# diybmsv4-00_panels.net
KiCad netlist of a schematic drawn in EAGLE
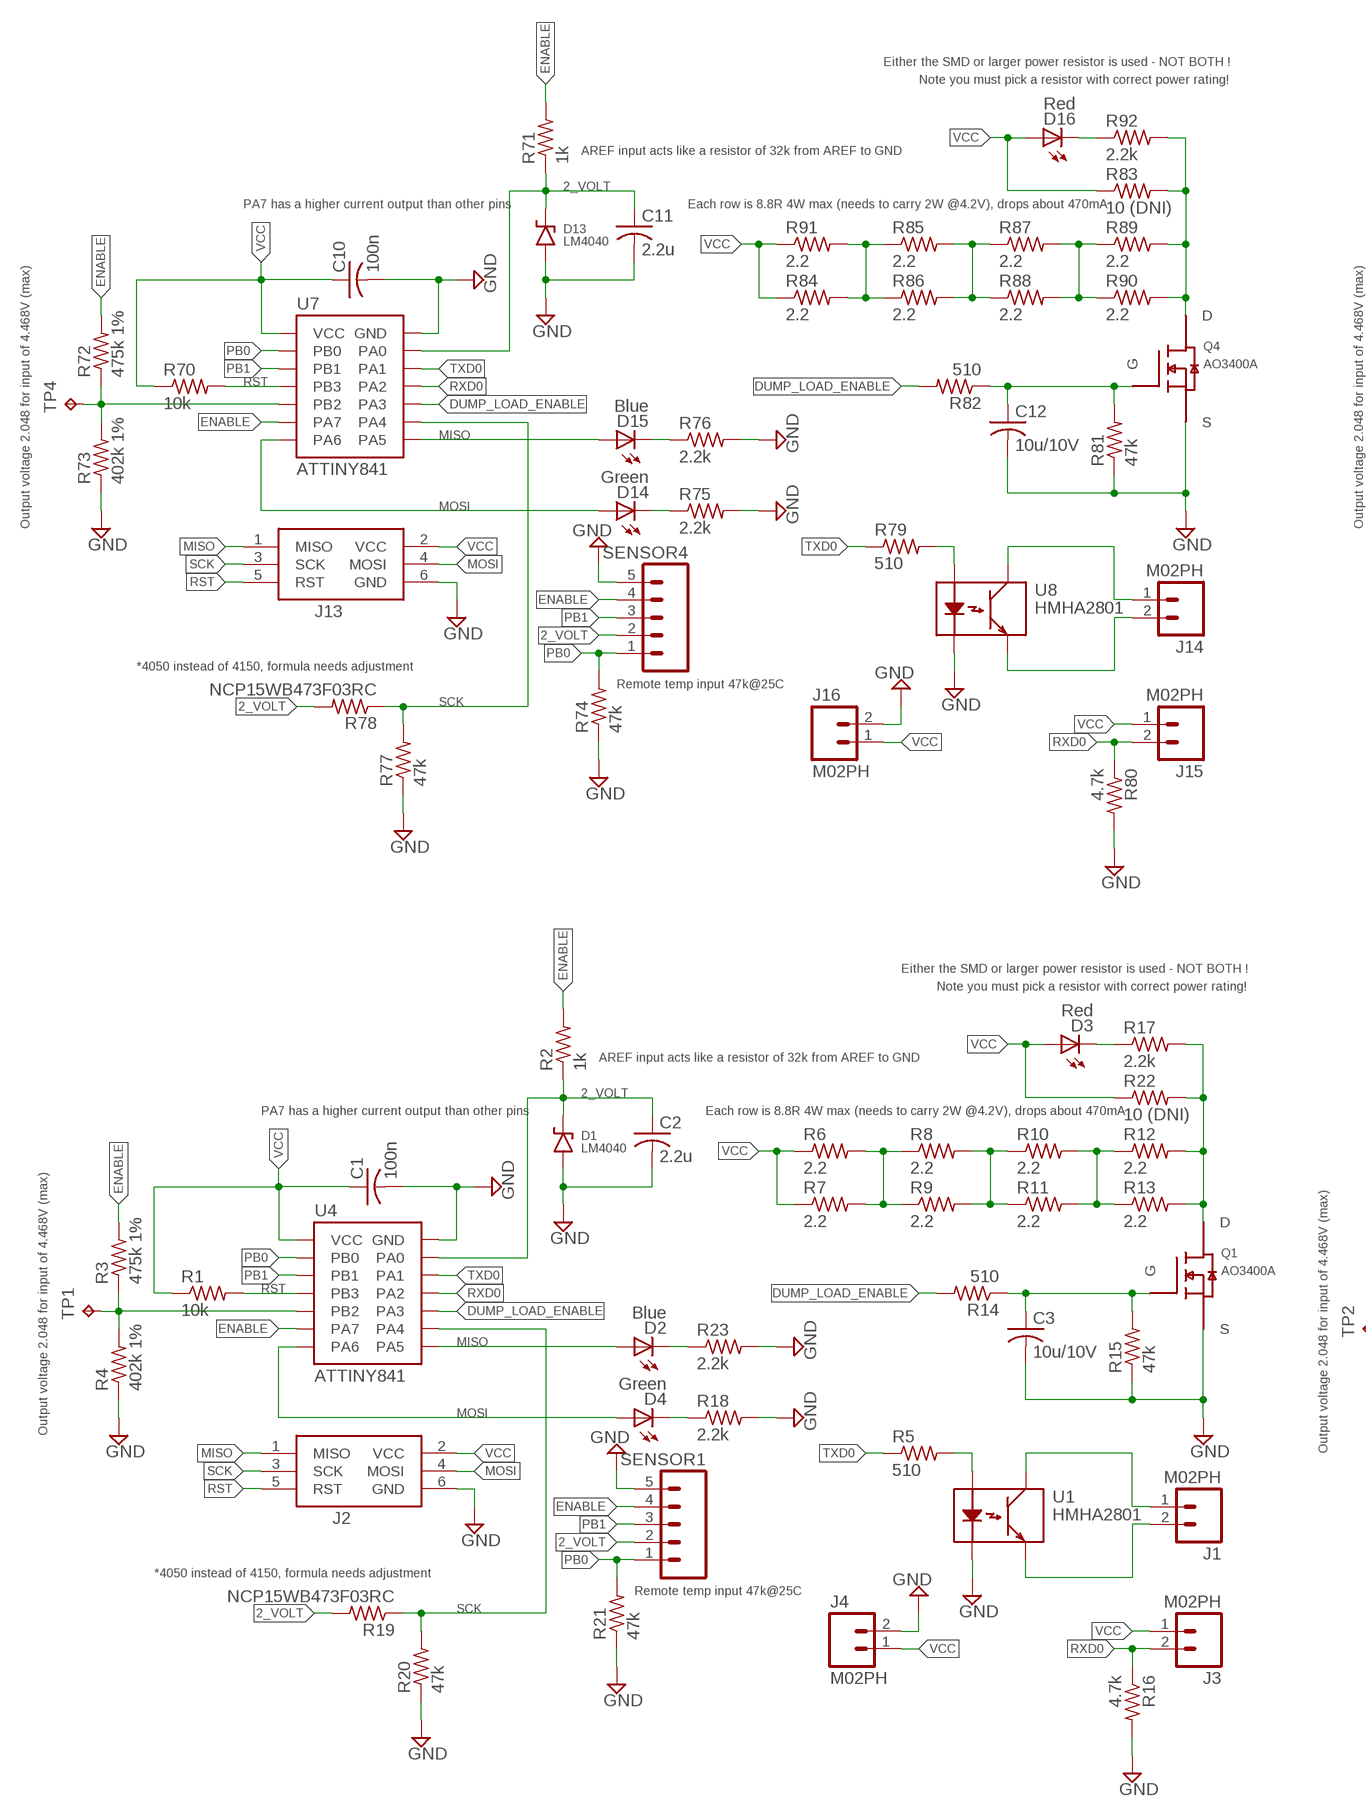
[diagram p0: schematic, sheet 1, part 1 of 2]
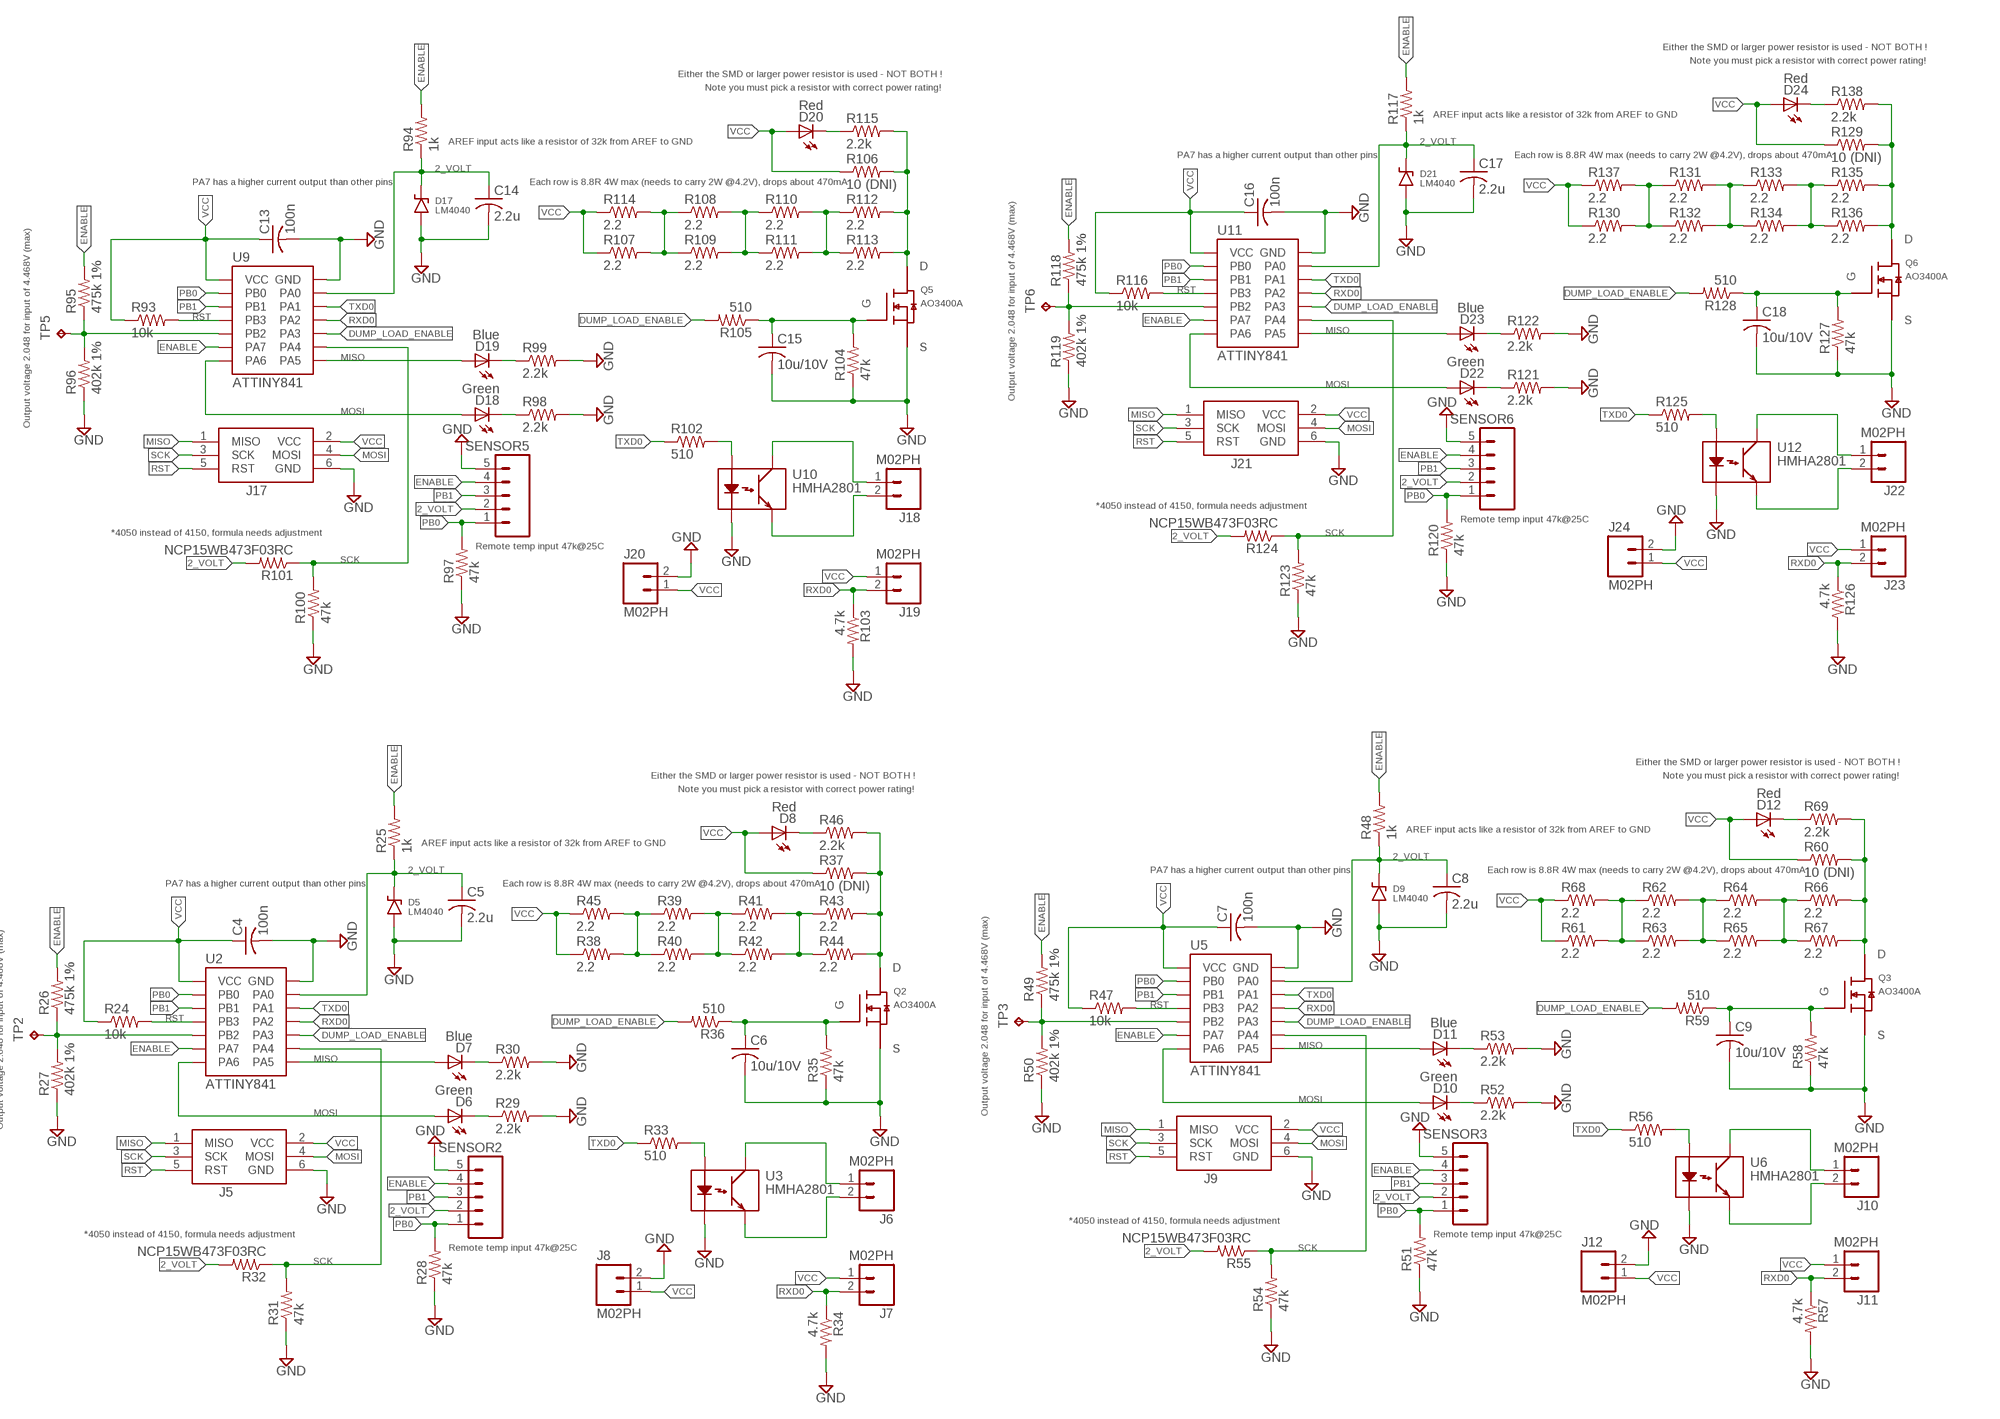
[diagram p1: schematic, sheet 1, part 2 of 2]

(export (version "E")
  (design (tool "Eeschema 10.0.6"))
  (components
    (comp (ref "C1")
      (value "100n")
      (footprint "eagle-import:C0402")
      (libsource (lib "eagle-import") (part "C-USC0402"))
    )
    (comp (ref "C2")
      (value "2.2u")
      (footprint "eagle-import:C0402")
      (libsource (lib "eagle-import") (part "C-USC0402"))
    )
    (comp (ref "C3")
      (value "10u/10V")
      (footprint "eagle-import:C0402")
      (libsource (lib "eagle-import") (part "C-USC0402"))
    )
    (comp (ref "C4")
      (value "100n")
      (footprint "eagle-import:C0402")
      (libsource (lib "eagle-import") (part "C-USC0402"))
    )
    (comp (ref "C5")
      (value "2.2u")
      (footprint "eagle-import:C0402")
      (libsource (lib "eagle-import") (part "C-USC0402"))
    )
    (comp (ref "C6")
      (value "10u/10V")
      (footprint "eagle-import:C0402")
      (libsource (lib "eagle-import") (part "C-USC0402"))
    )
    (comp (ref "C7")
      (value "100n")
      (footprint "eagle-import:C0402")
      (libsource (lib "eagle-import") (part "C-USC0402"))
    )
    (comp (ref "C8")
      (value "2.2u")
      (footprint "eagle-import:C0402")
      (libsource (lib "eagle-import") (part "C-USC0402"))
    )
    (comp (ref "C9")
      (value "10u/10V")
      (footprint "eagle-import:C0402")
      (libsource (lib "eagle-import") (part "C-USC0402"))
    )
    (comp (ref "C10")
      (value "100n")
      (footprint "eagle-import:C0402")
      (libsource (lib "eagle-import") (part "C-USC0402"))
    )
    (comp (ref "C11")
      (value "2.2u")
      (footprint "eagle-import:C0402")
      (libsource (lib "eagle-import") (part "C-USC0402"))
    )
    (comp (ref "C12")
      (value "10u/10V")
      (footprint "eagle-import:C0402")
      (libsource (lib "eagle-import") (part "C-USC0402"))
    )
    (comp (ref "C13")
      (value "100n")
      (footprint "eagle-import:C0402")
      (libsource (lib "eagle-import") (part "C-USC0402"))
    )
    (comp (ref "C14")
      (value "2.2u")
      (footprint "eagle-import:C0402")
      (libsource (lib "eagle-import") (part "C-USC0402"))
    )
    (comp (ref "C15")
      (value "10u/10V")
      (footprint "eagle-import:C0402")
      (libsource (lib "eagle-import") (part "C-USC0402"))
    )
    (comp (ref "C16")
      (value "100n")
      (footprint "eagle-import:C0402")
      (libsource (lib "eagle-import") (part "C-USC0402"))
    )
    (comp (ref "C17")
      (value "2.2u")
      (footprint "eagle-import:C0402")
      (libsource (lib "eagle-import") (part "C-USC0402"))
    )
    (comp (ref "C18")
      (value "10u/10V")
      (footprint "eagle-import:C0402")
      (libsource (lib "eagle-import") (part "C-USC0402"))
    )
    (comp (ref "D1")
      (value "LM4040")
      (footprint "eagle-import:SOT23")
      (libsource (lib "eagle-import") (part "LM4040"))
    )
    (comp (ref "D2")
      (value "Blue")
      (footprint "eagle-import:CHIPLED_0603")
      (libsource (lib "eagle-import") (part "LEDCHIPLED_0603"))
    )
    (comp (ref "D3")
      (value "Red")
      (footprint "eagle-import:CHIPLED_0603")
      (libsource (lib "eagle-import") (part "LEDCHIPLED_0603"))
    )
    (comp (ref "D4")
      (value "Green")
      (footprint "eagle-import:CHIPLED_0603")
      (libsource (lib "eagle-import") (part "LEDCHIPLED_0603"))
    )
    (comp (ref "D5")
      (value "LM4040")
      (footprint "eagle-import:SOT23")
      (libsource (lib "eagle-import") (part "LM4040"))
    )
    (comp (ref "D6")
      (value "Green")
      (footprint "eagle-import:CHIPLED_0603")
      (libsource (lib "eagle-import") (part "LEDCHIPLED_0603"))
    )
    (comp (ref "D7")
      (value "Blue")
      (footprint "eagle-import:CHIPLED_0603")
      (libsource (lib "eagle-import") (part "LEDCHIPLED_0603"))
    )
    (comp (ref "D8")
      (value "Red")
      (footprint "eagle-import:CHIPLED_0603")
      (libsource (lib "eagle-import") (part "LEDCHIPLED_0603"))
    )
    (comp (ref "D9")
      (value "LM4040")
      (footprint "eagle-import:SOT23")
      (libsource (lib "eagle-import") (part "LM4040"))
    )
    (comp (ref "D10")
      (value "Green")
      (footprint "eagle-import:CHIPLED_0603")
      (libsource (lib "eagle-import") (part "LEDCHIPLED_0603"))
    )
    (comp (ref "D11")
      (value "Blue")
      (footprint "eagle-import:CHIPLED_0603")
      (libsource (lib "eagle-import") (part "LEDCHIPLED_0603"))
    )
    (comp (ref "D12")
      (value "Red")
      (footprint "eagle-import:CHIPLED_0603")
      (libsource (lib "eagle-import") (part "LEDCHIPLED_0603"))
    )
    (comp (ref "D13")
      (value "LM4040")
      (footprint "eagle-import:SOT23")
      (libsource (lib "eagle-import") (part "LM4040"))
    )
    (comp (ref "D14")
      (value "Green")
      (footprint "eagle-import:CHIPLED_0603")
      (libsource (lib "eagle-import") (part "LEDCHIPLED_0603"))
    )
    (comp (ref "D15")
      (value "Blue")
      (footprint "eagle-import:CHIPLED_0603")
      (libsource (lib "eagle-import") (part "LEDCHIPLED_0603"))
    )
    (comp (ref "D16")
      (value "Red")
      (footprint "eagle-import:CHIPLED_0603")
      (libsource (lib "eagle-import") (part "LEDCHIPLED_0603"))
    )
    (comp (ref "D17")
      (value "LM4040")
      (footprint "eagle-import:SOT23")
      (libsource (lib "eagle-import") (part "LM4040"))
    )
    (comp (ref "D18")
      (value "Green")
      (footprint "eagle-import:CHIPLED_0603")
      (libsource (lib "eagle-import") (part "LEDCHIPLED_0603"))
    )
    (comp (ref "D19")
      (value "Blue")
      (footprint "eagle-import:CHIPLED_0603")
      (libsource (lib "eagle-import") (part "LEDCHIPLED_0603"))
    )
    (comp (ref "D20")
      (value "Red")
      (footprint "eagle-import:CHIPLED_0603")
      (libsource (lib "eagle-import") (part "LEDCHIPLED_0603"))
    )
    (comp (ref "D21")
      (value "LM4040")
      (footprint "eagle-import:SOT23")
      (libsource (lib "eagle-import") (part "LM4040"))
    )
    (comp (ref "D22")
      (value "Green")
      (footprint "eagle-import:CHIPLED_0603")
      (libsource (lib "eagle-import") (part "LEDCHIPLED_0603"))
    )
    (comp (ref "D23")
      (value "Blue")
      (footprint "eagle-import:CHIPLED_0603")
      (libsource (lib "eagle-import") (part "LEDCHIPLED_0603"))
    )
    (comp (ref "D24")
      (value "Red")
      (footprint "eagle-import:CHIPLED_0603")
      (libsource (lib "eagle-import") (part "LEDCHIPLED_0603"))
    )
    (comp (ref "J1")
      (value "M02PH")
      (footprint "eagle-import:S2B-PH-RA")
      (libsource (lib "eagle-import") (part "M02PH"))
    )
    (comp (ref "J2")
      (value "AVRISP-6")
      (footprint "eagle-import:AVRISP")
      (libsource (lib "eagle-import") (part "AVRISP-6"))
    )
    (comp (ref "J3")
      (value "M02PH")
      (footprint "eagle-import:S2B-PH-RA")
      (libsource (lib "eagle-import") (part "M02PH"))
    )
    (comp (ref "J4")
      (value "M02PH")
      (footprint "eagle-import:S2B-PH-RA")
      (libsource (lib "eagle-import") (part "M02PH"))
    )
    (comp (ref "J5")
      (value "AVRISP-6")
      (footprint "eagle-import:AVRISP")
      (libsource (lib "eagle-import") (part "AVRISP-6"))
    )
    (comp (ref "J6")
      (value "M02PH")
      (footprint "eagle-import:S2B-PH-RA")
      (libsource (lib "eagle-import") (part "M02PH"))
    )
    (comp (ref "J7")
      (value "M02PH")
      (footprint "eagle-import:S2B-PH-RA")
      (libsource (lib "eagle-import") (part "M02PH"))
    )
    (comp (ref "J8")
      (value "M02PH")
      (footprint "eagle-import:S2B-PH-RA")
      (libsource (lib "eagle-import") (part "M02PH"))
    )
    (comp (ref "J9")
      (value "AVRISP-6")
      (footprint "eagle-import:AVRISP")
      (libsource (lib "eagle-import") (part "AVRISP-6"))
    )
    (comp (ref "J10")
      (value "M02PH")
      (footprint "eagle-import:S2B-PH-RA")
      (libsource (lib "eagle-import") (part "M02PH"))
    )
    (comp (ref "J11")
      (value "M02PH")
      (footprint "eagle-import:S2B-PH-RA")
      (libsource (lib "eagle-import") (part "M02PH"))
    )
    (comp (ref "J12")
      (value "M02PH")
      (footprint "eagle-import:S2B-PH-RA")
      (libsource (lib "eagle-import") (part "M02PH"))
    )
    (comp (ref "J13")
      (value "AVRISP-6")
      (footprint "eagle-import:AVRISP")
      (libsource (lib "eagle-import") (part "AVRISP-6"))
    )
    (comp (ref "J14")
      (value "M02PH")
      (footprint "eagle-import:S2B-PH-RA")
      (libsource (lib "eagle-import") (part "M02PH"))
    )
    (comp (ref "J15")
      (value "M02PH")
      (footprint "eagle-import:S2B-PH-RA")
      (libsource (lib "eagle-import") (part "M02PH"))
    )
    (comp (ref "J16")
      (value "M02PH")
      (footprint "eagle-import:S2B-PH-RA")
      (libsource (lib "eagle-import") (part "M02PH"))
    )
    (comp (ref "J17")
      (value "AVRISP-6")
      (footprint "eagle-import:AVRISP")
      (libsource (lib "eagle-import") (part "AVRISP-6"))
    )
    (comp (ref "J18")
      (value "M02PH")
      (footprint "eagle-import:S2B-PH-RA")
      (libsource (lib "eagle-import") (part "M02PH"))
    )
    (comp (ref "J19")
      (value "M02PH")
      (footprint "eagle-import:S2B-PH-RA")
      (libsource (lib "eagle-import") (part "M02PH"))
    )
    (comp (ref "J20")
      (value "M02PH")
      (footprint "eagle-import:S2B-PH-RA")
      (libsource (lib "eagle-import") (part "M02PH"))
    )
    (comp (ref "J21")
      (value "AVRISP-6")
      (footprint "eagle-import:AVRISP")
      (libsource (lib "eagle-import") (part "AVRISP-6"))
    )
    (comp (ref "J22")
      (value "M02PH")
      (footprint "eagle-import:S2B-PH-RA")
      (libsource (lib "eagle-import") (part "M02PH"))
    )
    (comp (ref "J23")
      (value "M02PH")
      (footprint "eagle-import:S2B-PH-RA")
      (libsource (lib "eagle-import") (part "M02PH"))
    )
    (comp (ref "J24")
      (value "M02PH")
      (footprint "eagle-import:S2B-PH-RA")
      (libsource (lib "eagle-import") (part "M02PH"))
    )
    (comp (ref "Q1")
      (value "AO3400A")
      (footprint "eagle-import:SOT23")
      (libsource (lib "eagle-import") (part "AO3414"))
    )
    (comp (ref "Q2")
      (value "AO3400A")
      (footprint "eagle-import:SOT23")
      (libsource (lib "eagle-import") (part "AO3414"))
    )
    (comp (ref "Q3")
      (value "AO3400A")
      (footprint "eagle-import:SOT23")
      (libsource (lib "eagle-import") (part "AO3414"))
    )
    (comp (ref "Q4")
      (value "AO3400A")
      (footprint "eagle-import:SOT23")
      (libsource (lib "eagle-import") (part "AO3414"))
    )
    (comp (ref "Q5")
      (value "AO3400A")
      (footprint "eagle-import:SOT23")
      (libsource (lib "eagle-import") (part "AO3414"))
    )
    (comp (ref "Q6")
      (value "AO3400A")
      (footprint "eagle-import:SOT23")
      (libsource (lib "eagle-import") (part "AO3414"))
    )
    (comp (ref "R1")
      (value "10k")
      (footprint "eagle-import:R0402")
      (libsource (lib "eagle-import") (part "R-US_R0402"))
    )
    (comp (ref "R2")
      (value "1k")
      (footprint "eagle-import:R0402")
      (libsource (lib "eagle-import") (part "R-US_R0402"))
    )
    (comp (ref "R3")
      (value "475k 1%")
      (footprint "eagle-import:R0402")
      (libsource (lib "eagle-import") (part "R-US_R0402"))
    )
    (comp (ref "R4")
      (value "402k 1%")
      (footprint "eagle-import:R0402")
      (libsource (lib "eagle-import") (part "R-US_R0402"))
    )
    (comp (ref "R5")
      (value "510")
      (footprint "eagle-import:R0402")
      (libsource (lib "eagle-import") (part "R-US_R0402"))
    )
    (comp (ref "R6")
      (value "2.2")
      (footprint "eagle-import:R2512")
      (libsource (lib "eagle-import") (part "R-US_R2512"))
    )
    (comp (ref "R7")
      (value "2.2")
      (footprint "eagle-import:R2512")
      (libsource (lib "eagle-import") (part "R-US_R2512"))
    )
    (comp (ref "R8")
      (value "2.2")
      (footprint "eagle-import:R2512")
      (libsource (lib "eagle-import") (part "R-US_R2512"))
    )
    (comp (ref "R9")
      (value "2.2")
      (footprint "eagle-import:R2512")
      (libsource (lib "eagle-import") (part "R-US_R2512"))
    )
    (comp (ref "R10")
      (value "2.2")
      (footprint "eagle-import:R2512")
      (libsource (lib "eagle-import") (part "R-US_R2512"))
    )
    (comp (ref "R11")
      (value "2.2")
      (footprint "eagle-import:R2512")
      (libsource (lib "eagle-import") (part "R-US_R2512"))
    )
    (comp (ref "R12")
      (value "2.2")
      (footprint "eagle-import:R2512")
      (libsource (lib "eagle-import") (part "R-US_R2512"))
    )
    (comp (ref "R13")
      (value "2.2")
      (footprint "eagle-import:R2512")
      (libsource (lib "eagle-import") (part "R-US_R2512"))
    )
    (comp (ref "R14")
      (value "510")
      (footprint "eagle-import:R0402")
      (libsource (lib "eagle-import") (part "R-US_R0402"))
    )
    (comp (ref "R15")
      (value "47k")
      (footprint "eagle-import:R0402")
      (libsource (lib "eagle-import") (part "R-US_R0402"))
    )
    (comp (ref "R16")
      (value "4.7k")
      (footprint "eagle-import:R0402")
      (libsource (lib "eagle-import") (part "R-US_R0402"))
    )
    (comp (ref "R17")
      (value "2.2k")
      (footprint "eagle-import:R0402")
      (libsource (lib "eagle-import") (part "R-US_R0402"))
    )
    (comp (ref "R18")
      (value "2.2k")
      (footprint "eagle-import:R0402")
      (libsource (lib "eagle-import") (part "R-US_R0402"))
    )
    (comp (ref "R19")
      (value "NCP15WB473F03RC")
      (footprint "eagle-import:R0402")
      (libsource (lib "eagle-import") (part "R-US_R0402"))
    )
    (comp (ref "R20")
      (value "47k")
      (footprint "eagle-import:R0402")
      (libsource (lib "eagle-import") (part "R-US_R0402"))
    )
    (comp (ref "R21")
      (value "47k")
      (footprint "eagle-import:R0402")
      (libsource (lib "eagle-import") (part "R-US_R0402"))
    )
    (comp (ref "R22")
      (value "10 (DNI)")
      (footprint "eagle-import:R-5W-22X9P5X9P5")
      (libsource (lib "eagle-import") (part "RESISTOR25MM"))
    )
    (comp (ref "R23")
      (value "2.2k")
      (footprint "eagle-import:R0402")
      (libsource (lib "eagle-import") (part "R-US_R0402"))
    )
    (comp (ref "R24")
      (value "10k")
      (footprint "eagle-import:R0402")
      (libsource (lib "eagle-import") (part "R-US_R0402"))
    )
    (comp (ref "R25")
      (value "1k")
      (footprint "eagle-import:R0402")
      (libsource (lib "eagle-import") (part "R-US_R0402"))
    )
    (comp (ref "R26")
      (value "475k 1%")
      (footprint "eagle-import:R0402")
      (libsource (lib "eagle-import") (part "R-US_R0402"))
    )
    (comp (ref "R27")
      (value "402k 1%")
      (footprint "eagle-import:R0402")
      (libsource (lib "eagle-import") (part "R-US_R0402"))
    )
    (comp (ref "R28")
      (value "47k")
      (footprint "eagle-import:R0402")
      (libsource (lib "eagle-import") (part "R-US_R0402"))
    )
    (comp (ref "R29")
      (value "2.2k")
      (footprint "eagle-import:R0402")
      (libsource (lib "eagle-import") (part "R-US_R0402"))
    )
    (comp (ref "R30")
      (value "2.2k")
      (footprint "eagle-import:R0402")
      (libsource (lib "eagle-import") (part "R-US_R0402"))
    )
    (comp (ref "R31")
      (value "47k")
      (footprint "eagle-import:R0402")
      (libsource (lib "eagle-import") (part "R-US_R0402"))
    )
    (comp (ref "R32")
      (value "NCP15WB473F03RC")
      (footprint "eagle-import:R0402")
      (libsource (lib "eagle-import") (part "R-US_R0402"))
    )
    (comp (ref "R33")
      (value "510")
      (footprint "eagle-import:R0402")
      (libsource (lib "eagle-import") (part "R-US_R0402"))
    )
    (comp (ref "R34")
      (value "4.7k")
      (footprint "eagle-import:R0402")
      (libsource (lib "eagle-import") (part "R-US_R0402"))
    )
    (comp (ref "R35")
      (value "47k")
      (footprint "eagle-import:R0402")
      (libsource (lib "eagle-import") (part "R-US_R0402"))
    )
    (comp (ref "R36")
      (value "510")
      (footprint "eagle-import:R0402")
      (libsource (lib "eagle-import") (part "R-US_R0402"))
    )
    (comp (ref "R37")
      (value "10 (DNI)")
      (footprint "eagle-import:R-5W-22X9P5X9P5")
      (libsource (lib "eagle-import") (part "RESISTOR25MM"))
    )
    (comp (ref "R38")
      (value "2.2")
      (footprint "eagle-import:R2512")
      (libsource (lib "eagle-import") (part "R-US_R2512"))
    )
    (comp (ref "R39")
      (value "2.2")
      (footprint "eagle-import:R2512")
      (libsource (lib "eagle-import") (part "R-US_R2512"))
    )
    (comp (ref "R40")
      (value "2.2")
      (footprint "eagle-import:R2512")
      (libsource (lib "eagle-import") (part "R-US_R2512"))
    )
    (comp (ref "R41")
      (value "2.2")
      (footprint "eagle-import:R2512")
      (libsource (lib "eagle-import") (part "R-US_R2512"))
    )
    (comp (ref "R42")
      (value "2.2")
      (footprint "eagle-import:R2512")
      (libsource (lib "eagle-import") (part "R-US_R2512"))
    )
    (comp (ref "R43")
      (value "2.2")
      (footprint "eagle-import:R2512")
      (libsource (lib "eagle-import") (part "R-US_R2512"))
    )
    (comp (ref "R44")
      (value "2.2")
      (footprint "eagle-import:R2512")
      (libsource (lib "eagle-import") (part "R-US_R2512"))
    )
    (comp (ref "R45")
      (value "2.2")
      (footprint "eagle-import:R2512")
      (libsource (lib "eagle-import") (part "R-US_R2512"))
    )
    (comp (ref "R46")
      (value "2.2k")
      (footprint "eagle-import:R0402")
      (libsource (lib "eagle-import") (part "R-US_R0402"))
    )
    (comp (ref "R47")
      (value "10k")
      (footprint "eagle-import:R0402")
      (libsource (lib "eagle-import") (part "R-US_R0402"))
    )
    (comp (ref "R48")
      (value "1k")
      (footprint "eagle-import:R0402")
      (libsource (lib "eagle-import") (part "R-US_R0402"))
    )
    (comp (ref "R49")
      (value "475k 1%")
      (footprint "eagle-import:R0402")
      (libsource (lib "eagle-import") (part "R-US_R0402"))
    )
    (comp (ref "R50")
      (value "402k 1%")
      (footprint "eagle-import:R0402")
      (libsource (lib "eagle-import") (part "R-US_R0402"))
    )
    (comp (ref "R51")
      (value "47k")
      (footprint "eagle-import:R0402")
      (libsource (lib "eagle-import") (part "R-US_R0402"))
    )
    (comp (ref "R52")
      (value "2.2k")
      (footprint "eagle-import:R0402")
      (libsource (lib "eagle-import") (part "R-US_R0402"))
    )
    (comp (ref "R53")
      (value "2.2k")
      (footprint "eagle-import:R0402")
      (libsource (lib "eagle-import") (part "R-US_R0402"))
    )
    (comp (ref "R54")
      (value "47k")
      (footprint "eagle-import:R0402")
      (libsource (lib "eagle-import") (part "R-US_R0402"))
    )
    (comp (ref "R55")
      (value "NCP15WB473F03RC")
      (footprint "eagle-import:R0402")
      (libsource (lib "eagle-import") (part "R-US_R0402"))
    )
    (comp (ref "R56")
      (value "510")
      (footprint "eagle-import:R0402")
      (libsource (lib "eagle-import") (part "R-US_R0402"))
    )
    (comp (ref "R57")
      (value "4.7k")
      (footprint "eagle-import:R0402")
      (libsource (lib "eagle-import") (part "R-US_R0402"))
    )
    (comp (ref "R58")
      (value "47k")
      (footprint "eagle-import:R0402")
      (libsource (lib "eagle-import") (part "R-US_R0402"))
    )
    (comp (ref "R59")
      (value "510")
      (footprint "eagle-import:R0402")
      (libsource (lib "eagle-import") (part "R-US_R0402"))
    )
    (comp (ref "R60")
      (value "10 (DNI)")
      (footprint "eagle-import:R-5W-22X9P5X9P5")
      (libsource (lib "eagle-import") (part "RESISTOR25MM"))
    )
    (comp (ref "R61")
      (value "2.2")
      (footprint "eagle-import:R2512")
      (libsource (lib "eagle-import") (part "R-US_R2512"))
    )
    (comp (ref "R62")
      (value "2.2")
      (footprint "eagle-import:R2512")
      (libsource (lib "eagle-import") (part "R-US_R2512"))
    )
    (comp (ref "R63")
      (value "2.2")
      (footprint "eagle-import:R2512")
      (libsource (lib "eagle-import") (part "R-US_R2512"))
    )
    (comp (ref "R64")
      (value "2.2")
      (footprint "eagle-import:R2512")
      (libsource (lib "eagle-import") (part "R-US_R2512"))
    )
    (comp (ref "R65")
      (value "2.2")
      (footprint "eagle-import:R2512")
      (libsource (lib "eagle-import") (part "R-US_R2512"))
    )
    (comp (ref "R66")
      (value "2.2")
      (footprint "eagle-import:R2512")
      (libsource (lib "eagle-import") (part "R-US_R2512"))
    )
    (comp (ref "R67")
      (value "2.2")
      (footprint "eagle-import:R2512")
      (libsource (lib "eagle-import") (part "R-US_R2512"))
    )
    (comp (ref "R68")
      (value "2.2")
      (footprint "eagle-import:R2512")
      (libsource (lib "eagle-import") (part "R-US_R2512"))
    )
    (comp (ref "R69")
      (value "2.2k")
      (footprint "eagle-import:R0402")
      (libsource (lib "eagle-import") (part "R-US_R0402"))
    )
    (comp (ref "R70")
      (value "10k")
      (footprint "eagle-import:R0402")
      (libsource (lib "eagle-import") (part "R-US_R0402"))
    )
    (comp (ref "R71")
      (value "1k")
      (footprint "eagle-import:R0402")
      (libsource (lib "eagle-import") (part "R-US_R0402"))
    )
    (comp (ref "R72")
      (value "475k 1%")
      (footprint "eagle-import:R0402")
      (libsource (lib "eagle-import") (part "R-US_R0402"))
    )
    (comp (ref "R73")
      (value "402k 1%")
      (footprint "eagle-import:R0402")
      (libsource (lib "eagle-import") (part "R-US_R0402"))
    )
    (comp (ref "R74")
      (value "47k")
      (footprint "eagle-import:R0402")
      (libsource (lib "eagle-import") (part "R-US_R0402"))
    )
    (comp (ref "R75")
      (value "2.2k")
      (footprint "eagle-import:R0402")
      (libsource (lib "eagle-import") (part "R-US_R0402"))
    )
    (comp (ref "R76")
      (value "2.2k")
      (footprint "eagle-import:R0402")
      (libsource (lib "eagle-import") (part "R-US_R0402"))
    )
    (comp (ref "R77")
      (value "47k")
      (footprint "eagle-import:R0402")
      (libsource (lib "eagle-import") (part "R-US_R0402"))
    )
    (comp (ref "R78")
      (value "NCP15WB473F03RC")
      (footprint "eagle-import:R0402")
      (libsource (lib "eagle-import") (part "R-US_R0402"))
    )
    (comp (ref "R79")
      (value "510")
      (footprint "eagle-import:R0402")
      (libsource (lib "eagle-import") (part "R-US_R0402"))
    )
    (comp (ref "R80")
      (value "4.7k")
      (footprint "eagle-import:R0402")
      (libsource (lib "eagle-import") (part "R-US_R0402"))
    )
    (comp (ref "R81")
      (value "47k")
      (footprint "eagle-import:R0402")
      (libsource (lib "eagle-import") (part "R-US_R0402"))
    )
    (comp (ref "R82")
      (value "510")
      (footprint "eagle-import:R0402")
      (libsource (lib "eagle-import") (part "R-US_R0402"))
    )
    (comp (ref "R83")
      (value "10 (DNI)")
      (footprint "eagle-import:R-5W-22X9P5X9P5")
      (libsource (lib "eagle-import") (part "RESISTOR25MM"))
    )
    (comp (ref "R84")
      (value "2.2")
      (footprint "eagle-import:R2512")
      (libsource (lib "eagle-import") (part "R-US_R2512"))
    )
    (comp (ref "R85")
      (value "2.2")
      (footprint "eagle-import:R2512")
      (libsource (lib "eagle-import") (part "R-US_R2512"))
    )
    (comp (ref "R86")
      (value "2.2")
      (footprint "eagle-import:R2512")
      (libsource (lib "eagle-import") (part "R-US_R2512"))
    )
    (comp (ref "R87")
      (value "2.2")
      (footprint "eagle-import:R2512")
      (libsource (lib "eagle-import") (part "R-US_R2512"))
    )
    (comp (ref "R88")
      (value "2.2")
      (footprint "eagle-import:R2512")
      (libsource (lib "eagle-import") (part "R-US_R2512"))
    )
    (comp (ref "R89")
      (value "2.2")
      (footprint "eagle-import:R2512")
      (libsource (lib "eagle-import") (part "R-US_R2512"))
    )
    (comp (ref "R90")
      (value "2.2")
      (footprint "eagle-import:R2512")
      (libsource (lib "eagle-import") (part "R-US_R2512"))
    )
    (comp (ref "R91")
      (value "2.2")
      (footprint "eagle-import:R2512")
      (libsource (lib "eagle-import") (part "R-US_R2512"))
    )
    (comp (ref "R92")
      (value "2.2k")
      (footprint "eagle-import:R0402")
      (libsource (lib "eagle-import") (part "R-US_R0402"))
    )
    (comp (ref "R93")
      (value "10k")
      (footprint "eagle-import:R0402")
      (libsource (lib "eagle-import") (part "R-US_R0402"))
    )
    (comp (ref "R94")
      (value "1k")
      (footprint "eagle-import:R0402")
      (libsource (lib "eagle-import") (part "R-US_R0402"))
    )
    (comp (ref "R95")
      (value "475k 1%")
      (footprint "eagle-import:R0402")
      (libsource (lib "eagle-import") (part "R-US_R0402"))
    )
    (comp (ref "R96")
      (value "402k 1%")
      (footprint "eagle-import:R0402")
      (libsource (lib "eagle-import") (part "R-US_R0402"))
    )
    (comp (ref "R97")
      (value "47k")
      (footprint "eagle-import:R0402")
      (libsource (lib "eagle-import") (part "R-US_R0402"))
    )
    (comp (ref "R98")
      (value "2.2k")
      (footprint "eagle-import:R0402")
      (libsource (lib "eagle-import") (part "R-US_R0402"))
    )
    (comp (ref "R99")
      (value "2.2k")
      (footprint "eagle-import:R0402")
      (libsource (lib "eagle-import") (part "R-US_R0402"))
    )
    (comp (ref "R100")
      (value "47k")
      (footprint "eagle-import:R0402")
      (libsource (lib "eagle-import") (part "R-US_R0402"))
    )
    (comp (ref "R101")
      (value "NCP15WB473F03RC")
      (footprint "eagle-import:R0402")
      (libsource (lib "eagle-import") (part "R-US_R0402"))
    )
    (comp (ref "R102")
      (value "510")
      (footprint "eagle-import:R0402")
      (libsource (lib "eagle-import") (part "R-US_R0402"))
    )
    (comp (ref "R103")
      (value "4.7k")
      (footprint "eagle-import:R0402")
      (libsource (lib "eagle-import") (part "R-US_R0402"))
    )
    (comp (ref "R104")
      (value "47k")
      (footprint "eagle-import:R0402")
      (libsource (lib "eagle-import") (part "R-US_R0402"))
    )
    (comp (ref "R105")
      (value "510")
      (footprint "eagle-import:R0402")
      (libsource (lib "eagle-import") (part "R-US_R0402"))
    )
    (comp (ref "R106")
      (value "10 (DNI)")
      (footprint "eagle-import:R-5W-22X9P5X9P5")
      (libsource (lib "eagle-import") (part "RESISTOR25MM"))
    )
    (comp (ref "R107")
      (value "2.2")
      (footprint "eagle-import:R2512")
      (libsource (lib "eagle-import") (part "R-US_R2512"))
    )
    (comp (ref "R108")
      (value "2.2")
      (footprint "eagle-import:R2512")
      (libsource (lib "eagle-import") (part "R-US_R2512"))
    )
    (comp (ref "R109")
      (value "2.2")
      (footprint "eagle-import:R2512")
      (libsource (lib "eagle-import") (part "R-US_R2512"))
    )
    (comp (ref "R110")
      (value "2.2")
      (footprint "eagle-import:R2512")
      (libsource (lib "eagle-import") (part "R-US_R2512"))
    )
    (comp (ref "R111")
      (value "2.2")
      (footprint "eagle-import:R2512")
      (libsource (lib "eagle-import") (part "R-US_R2512"))
    )
    (comp (ref "R112")
      (value "2.2")
      (footprint "eagle-import:R2512")
      (libsource (lib "eagle-import") (part "R-US_R2512"))
    )
    (comp (ref "R113")
      (value "2.2")
      (footprint "eagle-import:R2512")
      (libsource (lib "eagle-import") (part "R-US_R2512"))
    )
    (comp (ref "R114")
      (value "2.2")
      (footprint "eagle-import:R2512")
      (libsource (lib "eagle-import") (part "R-US_R2512"))
    )
    (comp (ref "R115")
      (value "2.2k")
      (footprint "eagle-import:R0402")
      (libsource (lib "eagle-import") (part "R-US_R0402"))
    )
    (comp (ref "R116")
      (value "10k")
      (footprint "eagle-import:R0402")
      (libsource (lib "eagle-import") (part "R-US_R0402"))
    )
    (comp (ref "R117")
      (value "1k")
      (footprint "eagle-import:R0402")
      (libsource (lib "eagle-import") (part "R-US_R0402"))
    )
    (comp (ref "R118")
      (value "475k 1%")
      (footprint "eagle-import:R0402")
      (libsource (lib "eagle-import") (part "R-US_R0402"))
    )
    (comp (ref "R119")
      (value "402k 1%")
      (footprint "eagle-import:R0402")
      (libsource (lib "eagle-import") (part "R-US_R0402"))
    )
    (comp (ref "R120")
      (value "47k")
      (footprint "eagle-import:R0402")
      (libsource (lib "eagle-import") (part "R-US_R0402"))
    )
    (comp (ref "R121")
      (value "2.2k")
      (footprint "eagle-import:R0402")
      (libsource (lib "eagle-import") (part "R-US_R0402"))
    )
    (comp (ref "R122")
      (value "2.2k")
      (footprint "eagle-import:R0402")
      (libsource (lib "eagle-import") (part "R-US_R0402"))
    )
    (comp (ref "R123")
      (value "47k")
      (footprint "eagle-import:R0402")
      (libsource (lib "eagle-import") (part "R-US_R0402"))
    )
    (comp (ref "R124")
      (value "NCP15WB473F03RC")
      (footprint "eagle-import:R0402")
      (libsource (lib "eagle-import") (part "R-US_R0402"))
    )
    (comp (ref "R125")
      (value "510")
      (footprint "eagle-import:R0402")
      (libsource (lib "eagle-import") (part "R-US_R0402"))
    )
    (comp (ref "R126")
      (value "4.7k")
      (footprint "eagle-import:R0402")
      (libsource (lib "eagle-import") (part "R-US_R0402"))
    )
    (comp (ref "R127")
      (value "47k")
      (footprint "eagle-import:R0402")
      (libsource (lib "eagle-import") (part "R-US_R0402"))
    )
    (comp (ref "R128")
      (value "510")
      (footprint "eagle-import:R0402")
      (libsource (lib "eagle-import") (part "R-US_R0402"))
    )
    (comp (ref "R129")
      (value "10 (DNI)")
      (footprint "eagle-import:R-5W-22X9P5X9P5")
      (libsource (lib "eagle-import") (part "RESISTOR25MM"))
    )
    (comp (ref "R130")
      (value "2.2")
      (footprint "eagle-import:R2512")
      (libsource (lib "eagle-import") (part "R-US_R2512"))
    )
    (comp (ref "R131")
      (value "2.2")
      (footprint "eagle-import:R2512")
      (libsource (lib "eagle-import") (part "R-US_R2512"))
    )
    (comp (ref "R132")
      (value "2.2")
      (footprint "eagle-import:R2512")
      (libsource (lib "eagle-import") (part "R-US_R2512"))
    )
    (comp (ref "R133")
      (value "2.2")
      (footprint "eagle-import:R2512")
      (libsource (lib "eagle-import") (part "R-US_R2512"))
    )
    (comp (ref "R134")
      (value "2.2")
      (footprint "eagle-import:R2512")
      (libsource (lib "eagle-import") (part "R-US_R2512"))
    )
    (comp (ref "R135")
      (value "2.2")
      (footprint "eagle-import:R2512")
      (libsource (lib "eagle-import") (part "R-US_R2512"))
    )
    (comp (ref "R136")
      (value "2.2")
      (footprint "eagle-import:R2512")
      (libsource (lib "eagle-import") (part "R-US_R2512"))
    )
    (comp (ref "R137")
      (value "2.2")
      (footprint "eagle-import:R2512")
      (libsource (lib "eagle-import") (part "R-US_R2512"))
    )
    (comp (ref "R138")
      (value "2.2k")
      (footprint "eagle-import:R0402")
      (libsource (lib "eagle-import") (part "R-US_R0402"))
    )
    (comp (ref "SENSOR1")
      (value "M05PTH")
      (footprint "eagle-import:1X05")
      (libsource (lib "eagle-import") (part "M05PTH"))
    )
    (comp (ref "SENSOR2")
      (value "M05PTH")
      (footprint "eagle-import:1X05")
      (libsource (lib "eagle-import") (part "M05PTH"))
    )
    (comp (ref "SENSOR3")
      (value "M05PTH")
      (footprint "eagle-import:1X05")
      (libsource (lib "eagle-import") (part "M05PTH"))
    )
    (comp (ref "SENSOR4")
      (value "M05PTH")
      (footprint "eagle-import:1X05")
      (libsource (lib "eagle-import") (part "M05PTH"))
    )
    (comp (ref "SENSOR5")
      (value "M05PTH")
      (footprint "eagle-import:1X05")
      (libsource (lib "eagle-import") (part "M05PTH"))
    )
    (comp (ref "SENSOR6")
      (value "M05PTH")
      (footprint "eagle-import:1X05")
      (libsource (lib "eagle-import") (part "M05PTH"))
    )
    (comp (ref "TP1")
      (value "TPTP15SQ")
      (footprint "eagle-import:TP15SQ")
      (libsource (lib "eagle-import") (part "TPTP15SQ"))
    )
    (comp (ref "TP2")
      (value "TPTP15SQ")
      (footprint "eagle-import:TP15SQ")
      (libsource (lib "eagle-import") (part "TPTP15SQ"))
    )
    (comp (ref "TP3")
      (value "TPTP15SQ")
      (footprint "eagle-import:TP15SQ")
      (libsource (lib "eagle-import") (part "TPTP15SQ"))
    )
    (comp (ref "TP4")
      (value "TPTP15SQ")
      (footprint "eagle-import:TP15SQ")
      (libsource (lib "eagle-import") (part "TPTP15SQ"))
    )
    (comp (ref "TP5")
      (value "TPTP15SQ")
      (footprint "eagle-import:TP15SQ")
      (libsource (lib "eagle-import") (part "TPTP15SQ"))
    )
    (comp (ref "TP6")
      (value "TPTP15SQ")
      (footprint "eagle-import:TP15SQ")
      (libsource (lib "eagle-import") (part "TPTP15SQ"))
    )
    (comp (ref "U1")
      (value "HMHA2801")
      (footprint "eagle-import:4-SOIC")
      (libsource (lib "eagle-import") (part "HMHA2801"))
    )
    (comp (ref "U2")
      (value "ATTINY841")
      (footprint "eagle-import:14-SOIC")
      (libsource (lib "eagle-import") (part "ATTINY841"))
    )
    (comp (ref "U3")
      (value "HMHA2801")
      (footprint "eagle-import:4-SOIC")
      (libsource (lib "eagle-import") (part "HMHA2801"))
    )
    (comp (ref "U4")
      (value "ATTINY841")
      (footprint "eagle-import:14-SOIC")
      (libsource (lib "eagle-import") (part "ATTINY841"))
    )
    (comp (ref "U5")
      (value "ATTINY841")
      (footprint "eagle-import:14-SOIC")
      (libsource (lib "eagle-import") (part "ATTINY841"))
    )
    (comp (ref "U6")
      (value "HMHA2801")
      (footprint "eagle-import:4-SOIC")
      (libsource (lib "eagle-import") (part "HMHA2801"))
    )
    (comp (ref "U7")
      (value "ATTINY841")
      (footprint "eagle-import:14-SOIC")
      (libsource (lib "eagle-import") (part "ATTINY841"))
    )
    (comp (ref "U8")
      (value "HMHA2801")
      (footprint "eagle-import:4-SOIC")
      (libsource (lib "eagle-import") (part "HMHA2801"))
    )
    (comp (ref "U9")
      (value "ATTINY841")
      (footprint "eagle-import:14-SOIC")
      (libsource (lib "eagle-import") (part "ATTINY841"))
    )
    (comp (ref "U10")
      (value "HMHA2801")
      (footprint "eagle-import:4-SOIC")
      (libsource (lib "eagle-import") (part "HMHA2801"))
    )
    (comp (ref "U11")
      (value "ATTINY841")
      (footprint "eagle-import:14-SOIC")
      (libsource (lib "eagle-import") (part "ATTINY841"))
    )
    (comp (ref "U12")
      (value "HMHA2801")
      (footprint "eagle-import:4-SOIC")
      (libsource (lib "eagle-import") (part "HMHA2801"))
    )
  )
  (nets
    (net (code "1") (name "2_VOLT") (class "Default")
      (node (ref "C11") (pin "1") (pinfunction "1_1") (pintype "passive"))
      (node (ref "C14") (pin "1") (pinfunction "1_1") (pintype "passive"))
      (node (ref "C17") (pin "1") (pinfunction "1_1") (pintype "passive"))
      (node (ref "C2") (pin "1") (pinfunction "1_1") (pintype "passive"))
      (node (ref "C5") (pin "1") (pinfunction "1_1") (pintype "passive"))
      (node (ref "C8") (pin "1") (pinfunction "1_1") (pintype "passive"))
      (node (ref "D1") (pin "1") (pinfunction "K_1") (pintype "passive"))
      (node (ref "D13") (pin "1") (pinfunction "K_1") (pintype "passive"))
      (node (ref "D17") (pin "1") (pinfunction "K_1") (pintype "passive"))
      (node (ref "D21") (pin "1") (pinfunction "K_1") (pintype "passive"))
      (node (ref "D5") (pin "1") (pinfunction "K_1") (pintype "passive"))
      (node (ref "D9") (pin "1") (pinfunction "K_1") (pintype "passive"))
      (node (ref "R101") (pin "2") (pinfunction "2_2") (pintype "passive"))
      (node (ref "R117") (pin "1") (pinfunction "1_1") (pintype "passive"))
      (node (ref "R124") (pin "2") (pinfunction "2_2") (pintype "passive"))
      (node (ref "R19") (pin "2") (pinfunction "2_2") (pintype "passive"))
      (node (ref "R2") (pin "1") (pinfunction "1_1") (pintype "passive"))
      (node (ref "R25") (pin "1") (pinfunction "1_1") (pintype "passive"))
      (node (ref "R32") (pin "2") (pinfunction "2_2") (pintype "passive"))
      (node (ref "R48") (pin "1") (pinfunction "1_1") (pintype "passive"))
      (node (ref "R55") (pin "2") (pinfunction "2_2") (pintype "passive"))
      (node (ref "R71") (pin "1") (pinfunction "1_1") (pintype "passive"))
      (node (ref "R78") (pin "2") (pinfunction "2_2") (pintype "passive"))
      (node (ref "R94") (pin "1") (pinfunction "1_1") (pintype "passive"))
      (node (ref "SENSOR1") (pin "2") (pinfunction "2_2") (pintype "passive"))
      (node (ref "SENSOR2") (pin "2") (pinfunction "2_2") (pintype "passive"))
      (node (ref "SENSOR3") (pin "2") (pinfunction "2_2") (pintype "passive"))
      (node (ref "SENSOR4") (pin "2") (pinfunction "2_2") (pintype "passive"))
      (node (ref "SENSOR5") (pin "2") (pinfunction "2_2") (pintype "passive"))
      (node (ref "SENSOR6") (pin "2") (pinfunction "2_2") (pintype "passive"))
      (node (ref "U11") (pin "13") (pinfunction "PA0_13") (pintype "bidirectional"))
      (node (ref "U2") (pin "13") (pinfunction "PA0_13") (pintype "bidirectional"))
      (node (ref "U4") (pin "13") (pinfunction "PA0_13") (pintype "bidirectional"))
      (node (ref "U5") (pin "13") (pinfunction "PA0_13") (pintype "bidirectional"))
      (node (ref "U7") (pin "13") (pinfunction "PA0_13") (pintype "bidirectional"))
      (node (ref "U9") (pin "13") (pinfunction "PA0_13") (pintype "bidirectional"))
    )
    (net (code "2") (name "DUMP_LOAD_ENABLE") (class "Default")
      (node (ref "R105") (pin "2") (pinfunction "2_2") (pintype "passive"))
      (node (ref "R128") (pin "2") (pinfunction "2_2") (pintype "passive"))
      (node (ref "R14") (pin "2") (pinfunction "2_2") (pintype "passive"))
      (node (ref "R36") (pin "2") (pinfunction "2_2") (pintype "passive"))
      (node (ref "R59") (pin "2") (pinfunction "2_2") (pintype "passive"))
      (node (ref "R82") (pin "2") (pinfunction "2_2") (pintype "passive"))
      (node (ref "U11") (pin "10") (pinfunction "PA3_10") (pintype "bidirectional"))
      (node (ref "U2") (pin "10") (pinfunction "PA3_10") (pintype "bidirectional"))
      (node (ref "U4") (pin "10") (pinfunction "PA3_10") (pintype "bidirectional"))
      (node (ref "U5") (pin "10") (pinfunction "PA3_10") (pintype "bidirectional"))
      (node (ref "U7") (pin "10") (pinfunction "PA3_10") (pintype "bidirectional"))
      (node (ref "U9") (pin "10") (pinfunction "PA3_10") (pintype "bidirectional"))
    )
    (net (code "3") (name "ENABLE") (class "Default")
      (node (ref "R117") (pin "2") (pinfunction "2_2") (pintype "passive"))
      (node (ref "R118") (pin "2") (pinfunction "2_2") (pintype "passive"))
      (node (ref "R2") (pin "2") (pinfunction "2_2") (pintype "passive"))
      (node (ref "R25") (pin "2") (pinfunction "2_2") (pintype "passive"))
      (node (ref "R26") (pin "2") (pinfunction "2_2") (pintype "passive"))
      (node (ref "R3") (pin "2") (pinfunction "2_2") (pintype "passive"))
      (node (ref "R48") (pin "2") (pinfunction "2_2") (pintype "passive"))
      (node (ref "R49") (pin "2") (pinfunction "2_2") (pintype "passive"))
      (node (ref "R71") (pin "2") (pinfunction "2_2") (pintype "passive"))
      (node (ref "R72") (pin "2") (pinfunction "2_2") (pintype "passive"))
      (node (ref "R94") (pin "2") (pinfunction "2_2") (pintype "passive"))
      (node (ref "R95") (pin "2") (pinfunction "2_2") (pintype "passive"))
      (node (ref "SENSOR1") (pin "4") (pinfunction "4_4") (pintype "passive"))
      (node (ref "SENSOR2") (pin "4") (pinfunction "4_4") (pintype "passive"))
      (node (ref "SENSOR3") (pin "4") (pinfunction "4_4") (pintype "passive"))
      (node (ref "SENSOR4") (pin "4") (pinfunction "4_4") (pintype "passive"))
      (node (ref "SENSOR5") (pin "4") (pinfunction "4_4") (pintype "passive"))
      (node (ref "SENSOR6") (pin "4") (pinfunction "4_4") (pintype "passive"))
      (node (ref "U11") (pin "6") (pinfunction "PA7_6") (pintype "bidirectional"))
      (node (ref "U2") (pin "6") (pinfunction "PA7_6") (pintype "bidirectional"))
      (node (ref "U4") (pin "6") (pinfunction "PA7_6") (pintype "bidirectional"))
      (node (ref "U5") (pin "6") (pinfunction "PA7_6") (pintype "bidirectional"))
      (node (ref "U7") (pin "6") (pinfunction "PA7_6") (pintype "bidirectional"))
      (node (ref "U9") (pin "6") (pinfunction "PA7_6") (pintype "bidirectional"))
    )
    (net (code "4") (name "GND") (class "Default")
      (node (ref "C1") (pin "2") (pinfunction "2_2") (pintype "passive"))
      (node (ref "C10") (pin "2") (pinfunction "2_2") (pintype "passive"))
      (node (ref "C11") (pin "2") (pinfunction "2_2") (pintype "passive"))
      (node (ref "C12") (pin "2") (pinfunction "2_2") (pintype "passive"))
      (node (ref "C13") (pin "2") (pinfunction "2_2") (pintype "passive"))
      (node (ref "C14") (pin "2") (pinfunction "2_2") (pintype "passive"))
      (node (ref "C15") (pin "2") (pinfunction "2_2") (pintype "passive"))
      (node (ref "C16") (pin "2") (pinfunction "2_2") (pintype "passive"))
      (node (ref "C17") (pin "2") (pinfunction "2_2") (pintype "passive"))
      (node (ref "C18") (pin "2") (pinfunction "2_2") (pintype "passive"))
      (node (ref "C2") (pin "2") (pinfunction "2_2") (pintype "passive"))
      (node (ref "C3") (pin "2") (pinfunction "2_2") (pintype "passive"))
      (node (ref "C4") (pin "2") (pinfunction "2_2") (pintype "passive"))
      (node (ref "C5") (pin "2") (pinfunction "2_2") (pintype "passive"))
      (node (ref "C6") (pin "2") (pinfunction "2_2") (pintype "passive"))
      (node (ref "C7") (pin "2") (pinfunction "2_2") (pintype "passive"))
      (node (ref "C8") (pin "2") (pinfunction "2_2") (pintype "passive"))
      (node (ref "C9") (pin "2") (pinfunction "2_2") (pintype "passive"))
      (node (ref "D1") (pin "2") (pinfunction "A_2") (pintype "passive"))
      (node (ref "D13") (pin "2") (pinfunction "A_2") (pintype "passive"))
      (node (ref "D17") (pin "2") (pinfunction "A_2") (pintype "passive"))
      (node (ref "D21") (pin "2") (pinfunction "A_2") (pintype "passive"))
      (node (ref "D5") (pin "2") (pinfunction "A_2") (pintype "passive"))
      (node (ref "D9") (pin "2") (pinfunction "A_2") (pintype "passive"))
      (node (ref "J12") (pin "2") (pinfunction "2_2") (pintype "passive"))
      (node (ref "J13") (pin "6") (pinfunction "GND_6") (pintype "power_in"))
      (node (ref "J16") (pin "2") (pinfunction "2_2") (pintype "passive"))
      (node (ref "J17") (pin "6") (pinfunction "GND_6") (pintype "power_in"))
      (node (ref "J2") (pin "6") (pinfunction "GND_6") (pintype "power_in"))
      (node (ref "J20") (pin "2") (pinfunction "2_2") (pintype "passive"))
      (node (ref "J21") (pin "6") (pinfunction "GND_6") (pintype "power_in"))
      (node (ref "J24") (pin "2") (pinfunction "2_2") (pintype "passive"))
      (node (ref "J4") (pin "2") (pinfunction "2_2") (pintype "passive"))
      (node (ref "J5") (pin "6") (pinfunction "GND_6") (pintype "power_in"))
      (node (ref "J8") (pin "2") (pinfunction "2_2") (pintype "passive"))
      (node (ref "J9") (pin "6") (pinfunction "GND_6") (pintype "power_in"))
      (node (ref "Q1") (pin "2") (pinfunction "S_2") (pintype "bidirectional"))
      (node (ref "Q2") (pin "2") (pinfunction "S_2") (pintype "bidirectional"))
      (node (ref "Q3") (pin "2") (pinfunction "S_2") (pintype "bidirectional"))
      (node (ref "Q4") (pin "2") (pinfunction "S_2") (pintype "bidirectional"))
      (node (ref "Q5") (pin "2") (pinfunction "S_2") (pintype "bidirectional"))
      (node (ref "Q6") (pin "2") (pinfunction "S_2") (pintype "bidirectional"))
      (node (ref "R100") (pin "1") (pinfunction "1_1") (pintype "passive"))
      (node (ref "R103") (pin "2") (pinfunction "2_2") (pintype "passive"))
      (node (ref "R104") (pin "1") (pinfunction "1_1") (pintype "passive"))
      (node (ref "R119") (pin "1") (pinfunction "1_1") (pintype "passive"))
      (node (ref "R120") (pin "1") (pinfunction "1_1") (pintype "passive"))
      (node (ref "R121") (pin "2") (pinfunction "2_2") (pintype "passive"))
      (node (ref "R122") (pin "2") (pinfunction "2_2") (pintype "passive"))
      (node (ref "R123") (pin "1") (pinfunction "1_1") (pintype "passive"))
      (node (ref "R126") (pin "2") (pinfunction "2_2") (pintype "passive"))
      (node (ref "R127") (pin "1") (pinfunction "1_1") (pintype "passive"))
      (node (ref "R15") (pin "1") (pinfunction "1_1") (pintype "passive"))
      (node (ref "R16") (pin "2") (pinfunction "2_2") (pintype "passive"))
      (node (ref "R18") (pin "2") (pinfunction "2_2") (pintype "passive"))
      (node (ref "R20") (pin "1") (pinfunction "1_1") (pintype "passive"))
      (node (ref "R21") (pin "1") (pinfunction "1_1") (pintype "passive"))
      (node (ref "R23") (pin "2") (pinfunction "2_2") (pintype "passive"))
      (node (ref "R27") (pin "1") (pinfunction "1_1") (pintype "passive"))
      (node (ref "R28") (pin "1") (pinfunction "1_1") (pintype "passive"))
      (node (ref "R29") (pin "2") (pinfunction "2_2") (pintype "passive"))
      (node (ref "R30") (pin "2") (pinfunction "2_2") (pintype "passive"))
      (node (ref "R31") (pin "1") (pinfunction "1_1") (pintype "passive"))
      (node (ref "R34") (pin "2") (pinfunction "2_2") (pintype "passive"))
      (node (ref "R35") (pin "1") (pinfunction "1_1") (pintype "passive"))
      (node (ref "R4") (pin "1") (pinfunction "1_1") (pintype "passive"))
      (node (ref "R50") (pin "1") (pinfunction "1_1") (pintype "passive"))
      (node (ref "R51") (pin "1") (pinfunction "1_1") (pintype "passive"))
      (node (ref "R52") (pin "2") (pinfunction "2_2") (pintype "passive"))
      (node (ref "R53") (pin "2") (pinfunction "2_2") (pintype "passive"))
      (node (ref "R54") (pin "1") (pinfunction "1_1") (pintype "passive"))
      (node (ref "R57") (pin "2") (pinfunction "2_2") (pintype "passive"))
      (node (ref "R58") (pin "1") (pinfunction "1_1") (pintype "passive"))
      (node (ref "R73") (pin "1") (pinfunction "1_1") (pintype "passive"))
      (node (ref "R74") (pin "1") (pinfunction "1_1") (pintype "passive"))
      (node (ref "R75") (pin "2") (pinfunction "2_2") (pintype "passive"))
      (node (ref "R76") (pin "2") (pinfunction "2_2") (pintype "passive"))
      (node (ref "R77") (pin "1") (pinfunction "1_1") (pintype "passive"))
      (node (ref "R80") (pin "2") (pinfunction "2_2") (pintype "passive"))
      (node (ref "R81") (pin "1") (pinfunction "1_1") (pintype "passive"))
      (node (ref "R96") (pin "1") (pinfunction "1_1") (pintype "passive"))
      (node (ref "R97") (pin "1") (pinfunction "1_1") (pintype "passive"))
      (node (ref "R98") (pin "2") (pinfunction "2_2") (pintype "passive"))
      (node (ref "R99") (pin "2") (pinfunction "2_2") (pintype "passive"))
      (node (ref "SENSOR1") (pin "5") (pinfunction "5_5") (pintype "passive"))
      (node (ref "SENSOR2") (pin "5") (pinfunction "5_5") (pintype "passive"))
      (node (ref "SENSOR3") (pin "5") (pinfunction "5_5") (pintype "passive"))
      (node (ref "SENSOR4") (pin "5") (pinfunction "5_5") (pintype "passive"))
      (node (ref "SENSOR5") (pin "5") (pinfunction "5_5") (pintype "passive"))
      (node (ref "SENSOR6") (pin "5") (pinfunction "5_5") (pintype "passive"))
      (node (ref "U1") (pin "2") (pinfunction "K_2") (pintype "bidirectional"))
      (node (ref "U10") (pin "2") (pinfunction "K_2") (pintype "bidirectional"))
      (node (ref "U11") (pin "14") (pinfunction "GND_14") (pintype "bidirectional"))
      (node (ref "U12") (pin "2") (pinfunction "K_2") (pintype "bidirectional"))
      (node (ref "U2") (pin "14") (pinfunction "GND_14") (pintype "bidirectional"))
      (node (ref "U3") (pin "2") (pinfunction "K_2") (pintype "bidirectional"))
      (node (ref "U4") (pin "14") (pinfunction "GND_14") (pintype "bidirectional"))
      (node (ref "U5") (pin "14") (pinfunction "GND_14") (pintype "bidirectional"))
      (node (ref "U6") (pin "2") (pinfunction "K_2") (pintype "bidirectional"))
      (node (ref "U7") (pin "14") (pinfunction "GND_14") (pintype "bidirectional"))
      (node (ref "U8") (pin "2") (pinfunction "K_2") (pintype "bidirectional"))
      (node (ref "U9") (pin "14") (pinfunction "GND_14") (pintype "bidirectional"))
    )
    (net (code "5") (name "MISO") (class "Default")
      (node (ref "D11") (pin "A") (pinfunction "A_A") (pintype "passive"))
      (node (ref "D15") (pin "A") (pinfunction "A_A") (pintype "passive"))
      (node (ref "D19") (pin "A") (pinfunction "A_A") (pintype "passive"))
      (node (ref "D2") (pin "A") (pinfunction "A_A") (pintype "passive"))
      (node (ref "D23") (pin "A") (pinfunction "A_A") (pintype "passive"))
      (node (ref "D7") (pin "A") (pinfunction "A_A") (pintype "passive"))
      (node (ref "J13") (pin "1") (pinfunction "MISO_1") (pintype "input"))
      (node (ref "J17") (pin "1") (pinfunction "MISO_1") (pintype "input"))
      (node (ref "J2") (pin "1") (pinfunction "MISO_1") (pintype "input"))
      (node (ref "J21") (pin "1") (pinfunction "MISO_1") (pintype "input"))
      (node (ref "J5") (pin "1") (pinfunction "MISO_1") (pintype "input"))
      (node (ref "J9") (pin "1") (pinfunction "MISO_1") (pintype "input"))
      (node (ref "U11") (pin "8") (pinfunction "PA5_8") (pintype "bidirectional"))
      (node (ref "U2") (pin "8") (pinfunction "PA5_8") (pintype "bidirectional"))
      (node (ref "U4") (pin "8") (pinfunction "PA5_8") (pintype "bidirectional"))
      (node (ref "U5") (pin "8") (pinfunction "PA5_8") (pintype "bidirectional"))
      (node (ref "U7") (pin "8") (pinfunction "PA5_8") (pintype "bidirectional"))
      (node (ref "U9") (pin "8") (pinfunction "PA5_8") (pintype "bidirectional"))
    )
    (net (code "6") (name "MOSI") (class "Default")
      (node (ref "D10") (pin "A") (pinfunction "A_A") (pintype "passive"))
      (node (ref "D14") (pin "A") (pinfunction "A_A") (pintype "passive"))
      (node (ref "D18") (pin "A") (pinfunction "A_A") (pintype "passive"))
      (node (ref "D22") (pin "A") (pinfunction "A_A") (pintype "passive"))
      (node (ref "D4") (pin "A") (pinfunction "A_A") (pintype "passive"))
      (node (ref "D6") (pin "A") (pinfunction "A_A") (pintype "passive"))
      (node (ref "J13") (pin "4") (pinfunction "MOSI_4") (pintype "output"))
      (node (ref "J17") (pin "4") (pinfunction "MOSI_4") (pintype "output"))
      (node (ref "J2") (pin "4") (pinfunction "MOSI_4") (pintype "output"))
      (node (ref "J21") (pin "4") (pinfunction "MOSI_4") (pintype "output"))
      (node (ref "J5") (pin "4") (pinfunction "MOSI_4") (pintype "output"))
      (node (ref "J9") (pin "4") (pinfunction "MOSI_4") (pintype "output"))
      (node (ref "U11") (pin "7") (pinfunction "PA6_7") (pintype "bidirectional"))
      (node (ref "U2") (pin "7") (pinfunction "PA6_7") (pintype "bidirectional"))
      (node (ref "U4") (pin "7") (pinfunction "PA6_7") (pintype "bidirectional"))
      (node (ref "U5") (pin "7") (pinfunction "PA6_7") (pintype "bidirectional"))
      (node (ref "U7") (pin "7") (pinfunction "PA6_7") (pintype "bidirectional"))
      (node (ref "U9") (pin "7") (pinfunction "PA6_7") (pintype "bidirectional"))
    )
    (net (code "7") (name "Net-(D2-PadC)") (class "Default")
      (node (ref "D2") (pin "C") (pinfunction "C_C") (pintype "passive"))
      (node (ref "R23") (pin "1") (pinfunction "1_1") (pintype "passive"))
    )
    (net (code "8") (name "Net-(D3-PadC)") (class "Default")
      (node (ref "D3") (pin "C") (pinfunction "C_C") (pintype "passive"))
      (node (ref "R17") (pin "1") (pinfunction "1_1") (pintype "passive"))
    )
    (net (code "9") (name "Net-(D4-PadC)") (class "Default")
      (node (ref "D4") (pin "C") (pinfunction "C_C") (pintype "passive"))
      (node (ref "R18") (pin "1") (pinfunction "1_1") (pintype "passive"))
    )
    (net (code "10") (name "Net-(D6-PadC)") (class "Default")
      (node (ref "D6") (pin "C") (pinfunction "C_C") (pintype "passive"))
      (node (ref "R29") (pin "1") (pinfunction "1_1") (pintype "passive"))
    )
    (net (code "11") (name "Net-(D7-PadC)") (class "Default")
      (node (ref "D7") (pin "C") (pinfunction "C_C") (pintype "passive"))
      (node (ref "R30") (pin "1") (pinfunction "1_1") (pintype "passive"))
    )
    (net (code "12") (name "Net-(D8-PadC)") (class "Default")
      (node (ref "D8") (pin "C") (pinfunction "C_C") (pintype "passive"))
      (node (ref "R46") (pin "1") (pinfunction "1_1") (pintype "passive"))
    )
    (net (code "13") (name "Net-(D10-PadC)") (class "Default")
      (node (ref "D10") (pin "C") (pinfunction "C_C") (pintype "passive"))
      (node (ref "R52") (pin "1") (pinfunction "1_1") (pintype "passive"))
    )
    (net (code "14") (name "Net-(D11-PadC)") (class "Default")
      (node (ref "D11") (pin "C") (pinfunction "C_C") (pintype "passive"))
      (node (ref "R53") (pin "1") (pinfunction "1_1") (pintype "passive"))
    )
    (net (code "15") (name "Net-(D12-PadC)") (class "Default")
      (node (ref "D12") (pin "C") (pinfunction "C_C") (pintype "passive"))
      (node (ref "R69") (pin "1") (pinfunction "1_1") (pintype "passive"))
    )
    (net (code "16") (name "Net-(D14-PadC)") (class "Default")
      (node (ref "D14") (pin "C") (pinfunction "C_C") (pintype "passive"))
      (node (ref "R75") (pin "1") (pinfunction "1_1") (pintype "passive"))
    )
    (net (code "17") (name "Net-(D15-PadC)") (class "Default")
      (node (ref "D15") (pin "C") (pinfunction "C_C") (pintype "passive"))
      (node (ref "R76") (pin "1") (pinfunction "1_1") (pintype "passive"))
    )
    (net (code "18") (name "Net-(D16-PadC)") (class "Default")
      (node (ref "D16") (pin "C") (pinfunction "C_C") (pintype "passive"))
      (node (ref "R92") (pin "1") (pinfunction "1_1") (pintype "passive"))
    )
    (net (code "19") (name "Net-(D18-PadC)") (class "Default")
      (node (ref "D18") (pin "C") (pinfunction "C_C") (pintype "passive"))
      (node (ref "R98") (pin "1") (pinfunction "1_1") (pintype "passive"))
    )
    (net (code "20") (name "Net-(D19-PadC)") (class "Default")
      (node (ref "D19") (pin "C") (pinfunction "C_C") (pintype "passive"))
      (node (ref "R99") (pin "1") (pinfunction "1_1") (pintype "passive"))
    )
    (net (code "21") (name "Net-(D20-PadC)") (class "Default")
      (node (ref "D20") (pin "C") (pinfunction "C_C") (pintype "passive"))
      (node (ref "R115") (pin "1") (pinfunction "1_1") (pintype "passive"))
    )
    (net (code "22") (name "Net-(D22-PadC)") (class "Default")
      (node (ref "D22") (pin "C") (pinfunction "C_C") (pintype "passive"))
      (node (ref "R121") (pin "1") (pinfunction "1_1") (pintype "passive"))
    )
    (net (code "23") (name "Net-(D23-PadC)") (class "Default")
      (node (ref "D23") (pin "C") (pinfunction "C_C") (pintype "passive"))
      (node (ref "R122") (pin "1") (pinfunction "1_1") (pintype "passive"))
    )
    (net (code "24") (name "Net-(D24-PadC)") (class "Default")
      (node (ref "D24") (pin "C") (pinfunction "C_C") (pintype "passive"))
      (node (ref "R138") (pin "1") (pinfunction "1_1") (pintype "passive"))
    )
    (net (code "25") (name "Net-(Q1-D)") (class "Default")
      (node (ref "Q1") (pin "3") (pinfunction "D_3") (pintype "bidirectional"))
      (node (ref "R12") (pin "2") (pinfunction "2_2") (pintype "passive"))
      (node (ref "R13") (pin "2") (pinfunction "2_2") (pintype "passive"))
      (node (ref "R17") (pin "2") (pinfunction "2_2") (pintype "passive"))
      (node (ref "R22") (pin "2") (pinfunction "2_2") (pintype "passive"))
    )
    (net (code "26") (name "Net-(Q1-G)") (class "Default")
      (node (ref "C3") (pin "1") (pinfunction "1_1") (pintype "passive"))
      (node (ref "Q1") (pin "1") (pinfunction "G_1") (pintype "bidirectional"))
      (node (ref "R14") (pin "1") (pinfunction "1_1") (pintype "passive"))
      (node (ref "R15") (pin "2") (pinfunction "2_2") (pintype "passive"))
    )
    (net (code "27") (name "Net-(Q2-D)") (class "Default")
      (node (ref "Q2") (pin "3") (pinfunction "D_3") (pintype "bidirectional"))
      (node (ref "R37") (pin "2") (pinfunction "2_2") (pintype "passive"))
      (node (ref "R43") (pin "2") (pinfunction "2_2") (pintype "passive"))
      (node (ref "R44") (pin "2") (pinfunction "2_2") (pintype "passive"))
      (node (ref "R46") (pin "2") (pinfunction "2_2") (pintype "passive"))
    )
    (net (code "28") (name "Net-(Q2-G)") (class "Default")
      (node (ref "C6") (pin "1") (pinfunction "1_1") (pintype "passive"))
      (node (ref "Q2") (pin "1") (pinfunction "G_1") (pintype "bidirectional"))
      (node (ref "R35") (pin "2") (pinfunction "2_2") (pintype "passive"))
      (node (ref "R36") (pin "1") (pinfunction "1_1") (pintype "passive"))
    )
    (net (code "29") (name "Net-(Q3-D)") (class "Default")
      (node (ref "Q3") (pin "3") (pinfunction "D_3") (pintype "bidirectional"))
      (node (ref "R60") (pin "2") (pinfunction "2_2") (pintype "passive"))
      (node (ref "R66") (pin "2") (pinfunction "2_2") (pintype "passive"))
      (node (ref "R67") (pin "2") (pinfunction "2_2") (pintype "passive"))
      (node (ref "R69") (pin "2") (pinfunction "2_2") (pintype "passive"))
    )
    (net (code "30") (name "Net-(Q3-G)") (class "Default")
      (node (ref "C9") (pin "1") (pinfunction "1_1") (pintype "passive"))
      (node (ref "Q3") (pin "1") (pinfunction "G_1") (pintype "bidirectional"))
      (node (ref "R58") (pin "2") (pinfunction "2_2") (pintype "passive"))
      (node (ref "R59") (pin "1") (pinfunction "1_1") (pintype "passive"))
    )
    (net (code "31") (name "Net-(Q4-D)") (class "Default")
      (node (ref "Q4") (pin "3") (pinfunction "D_3") (pintype "bidirectional"))
      (node (ref "R83") (pin "2") (pinfunction "2_2") (pintype "passive"))
      (node (ref "R89") (pin "2") (pinfunction "2_2") (pintype "passive"))
      (node (ref "R90") (pin "2") (pinfunction "2_2") (pintype "passive"))
      (node (ref "R92") (pin "2") (pinfunction "2_2") (pintype "passive"))
    )
    (net (code "32") (name "Net-(Q4-G)") (class "Default")
      (node (ref "C12") (pin "1") (pinfunction "1_1") (pintype "passive"))
      (node (ref "Q4") (pin "1") (pinfunction "G_1") (pintype "bidirectional"))
      (node (ref "R81") (pin "2") (pinfunction "2_2") (pintype "passive"))
      (node (ref "R82") (pin "1") (pinfunction "1_1") (pintype "passive"))
    )
    (net (code "33") (name "Net-(Q5-D)") (class "Default")
      (node (ref "Q5") (pin "3") (pinfunction "D_3") (pintype "bidirectional"))
      (node (ref "R106") (pin "2") (pinfunction "2_2") (pintype "passive"))
      (node (ref "R112") (pin "2") (pinfunction "2_2") (pintype "passive"))
      (node (ref "R113") (pin "2") (pinfunction "2_2") (pintype "passive"))
      (node (ref "R115") (pin "2") (pinfunction "2_2") (pintype "passive"))
    )
    (net (code "34") (name "Net-(Q5-G)") (class "Default")
      (node (ref "C15") (pin "1") (pinfunction "1_1") (pintype "passive"))
      (node (ref "Q5") (pin "1") (pinfunction "G_1") (pintype "bidirectional"))
      (node (ref "R104") (pin "2") (pinfunction "2_2") (pintype "passive"))
      (node (ref "R105") (pin "1") (pinfunction "1_1") (pintype "passive"))
    )
    (net (code "35") (name "Net-(Q6-D)") (class "Default")
      (node (ref "Q6") (pin "3") (pinfunction "D_3") (pintype "bidirectional"))
      (node (ref "R129") (pin "2") (pinfunction "2_2") (pintype "passive"))
      (node (ref "R135") (pin "2") (pinfunction "2_2") (pintype "passive"))
      (node (ref "R136") (pin "2") (pinfunction "2_2") (pintype "passive"))
      (node (ref "R138") (pin "2") (pinfunction "2_2") (pintype "passive"))
    )
    (net (code "36") (name "Net-(Q6-G)") (class "Default")
      (node (ref "C18") (pin "1") (pinfunction "1_1") (pintype "passive"))
      (node (ref "Q6") (pin "1") (pinfunction "G_1") (pintype "bidirectional"))
      (node (ref "R127") (pin "2") (pinfunction "2_2") (pintype "passive"))
      (node (ref "R128") (pin "1") (pinfunction "1_1") (pintype "passive"))
    )
    (net (code "37") (name "Net-(R6-Pad2)") (class "Default")
      (node (ref "R6") (pin "2") (pinfunction "2_2") (pintype "passive"))
      (node (ref "R7") (pin "2") (pinfunction "2_2") (pintype "passive"))
      (node (ref "R8") (pin "1") (pinfunction "1_1") (pintype "passive"))
      (node (ref "R9") (pin "1") (pinfunction "1_1") (pintype "passive"))
    )
    (net (code "38") (name "Net-(R10-Pad1)") (class "Default")
      (node (ref "R10") (pin "1") (pinfunction "1_1") (pintype "passive"))
      (node (ref "R11") (pin "1") (pinfunction "1_1") (pintype "passive"))
      (node (ref "R8") (pin "2") (pinfunction "2_2") (pintype "passive"))
      (node (ref "R9") (pin "2") (pinfunction "2_2") (pintype "passive"))
    )
    (net (code "39") (name "Net-(R10-Pad2)") (class "Default")
      (node (ref "R10") (pin "2") (pinfunction "2_2") (pintype "passive"))
      (node (ref "R11") (pin "2") (pinfunction "2_2") (pintype "passive"))
      (node (ref "R12") (pin "1") (pinfunction "1_1") (pintype "passive"))
      (node (ref "R13") (pin "1") (pinfunction "1_1") (pintype "passive"))
    )
    (net (code "40") (name "Net-(R38-Pad2)") (class "Default")
      (node (ref "R38") (pin "2") (pinfunction "2_2") (pintype "passive"))
      (node (ref "R39") (pin "1") (pinfunction "1_1") (pintype "passive"))
      (node (ref "R40") (pin "1") (pinfunction "1_1") (pintype "passive"))
      (node (ref "R45") (pin "2") (pinfunction "2_2") (pintype "passive"))
    )
    (net (code "41") (name "Net-(R39-Pad2)") (class "Default")
      (node (ref "R39") (pin "2") (pinfunction "2_2") (pintype "passive"))
      (node (ref "R40") (pin "2") (pinfunction "2_2") (pintype "passive"))
      (node (ref "R41") (pin "1") (pinfunction "1_1") (pintype "passive"))
      (node (ref "R42") (pin "1") (pinfunction "1_1") (pintype "passive"))
    )
    (net (code "42") (name "Net-(R41-Pad2)") (class "Default")
      (node (ref "R41") (pin "2") (pinfunction "2_2") (pintype "passive"))
      (node (ref "R42") (pin "2") (pinfunction "2_2") (pintype "passive"))
      (node (ref "R43") (pin "1") (pinfunction "1_1") (pintype "passive"))
      (node (ref "R44") (pin "1") (pinfunction "1_1") (pintype "passive"))
    )
    (net (code "43") (name "Net-(R61-Pad2)") (class "Default")
      (node (ref "R61") (pin "2") (pinfunction "2_2") (pintype "passive"))
      (node (ref "R62") (pin "1") (pinfunction "1_1") (pintype "passive"))
      (node (ref "R63") (pin "1") (pinfunction "1_1") (pintype "passive"))
      (node (ref "R68") (pin "2") (pinfunction "2_2") (pintype "passive"))
    )
    (net (code "44") (name "Net-(R62-Pad2)") (class "Default")
      (node (ref "R62") (pin "2") (pinfunction "2_2") (pintype "passive"))
      (node (ref "R63") (pin "2") (pinfunction "2_2") (pintype "passive"))
      (node (ref "R64") (pin "1") (pinfunction "1_1") (pintype "passive"))
      (node (ref "R65") (pin "1") (pinfunction "1_1") (pintype "passive"))
    )
    (net (code "45") (name "Net-(R64-Pad2)") (class "Default")
      (node (ref "R64") (pin "2") (pinfunction "2_2") (pintype "passive"))
      (node (ref "R65") (pin "2") (pinfunction "2_2") (pintype "passive"))
      (node (ref "R66") (pin "1") (pinfunction "1_1") (pintype "passive"))
      (node (ref "R67") (pin "1") (pinfunction "1_1") (pintype "passive"))
    )
    (net (code "46") (name "Net-(R84-Pad2)") (class "Default")
      (node (ref "R84") (pin "2") (pinfunction "2_2") (pintype "passive"))
      (node (ref "R85") (pin "1") (pinfunction "1_1") (pintype "passive"))
      (node (ref "R86") (pin "1") (pinfunction "1_1") (pintype "passive"))
      (node (ref "R91") (pin "2") (pinfunction "2_2") (pintype "passive"))
    )
    (net (code "47") (name "Net-(R85-Pad2)") (class "Default")
      (node (ref "R85") (pin "2") (pinfunction "2_2") (pintype "passive"))
      (node (ref "R86") (pin "2") (pinfunction "2_2") (pintype "passive"))
      (node (ref "R87") (pin "1") (pinfunction "1_1") (pintype "passive"))
      (node (ref "R88") (pin "1") (pinfunction "1_1") (pintype "passive"))
    )
    (net (code "48") (name "Net-(R87-Pad2)") (class "Default")
      (node (ref "R87") (pin "2") (pinfunction "2_2") (pintype "passive"))
      (node (ref "R88") (pin "2") (pinfunction "2_2") (pintype "passive"))
      (node (ref "R89") (pin "1") (pinfunction "1_1") (pintype "passive"))
      (node (ref "R90") (pin "1") (pinfunction "1_1") (pintype "passive"))
    )
    (net (code "49") (name "Net-(R107-Pad2)") (class "Default")
      (node (ref "R107") (pin "2") (pinfunction "2_2") (pintype "passive"))
      (node (ref "R108") (pin "1") (pinfunction "1_1") (pintype "passive"))
      (node (ref "R109") (pin "1") (pinfunction "1_1") (pintype "passive"))
      (node (ref "R114") (pin "2") (pinfunction "2_2") (pintype "passive"))
    )
    (net (code "50") (name "Net-(R108-Pad2)") (class "Default")
      (node (ref "R108") (pin "2") (pinfunction "2_2") (pintype "passive"))
      (node (ref "R109") (pin "2") (pinfunction "2_2") (pintype "passive"))
      (node (ref "R110") (pin "1") (pinfunction "1_1") (pintype "passive"))
      (node (ref "R111") (pin "1") (pinfunction "1_1") (pintype "passive"))
    )
    (net (code "51") (name "Net-(R110-Pad2)") (class "Default")
      (node (ref "R110") (pin "2") (pinfunction "2_2") (pintype "passive"))
      (node (ref "R111") (pin "2") (pinfunction "2_2") (pintype "passive"))
      (node (ref "R112") (pin "1") (pinfunction "1_1") (pintype "passive"))
      (node (ref "R113") (pin "1") (pinfunction "1_1") (pintype "passive"))
    )
    (net (code "52") (name "Net-(R130-Pad2)") (class "Default")
      (node (ref "R130") (pin "2") (pinfunction "2_2") (pintype "passive"))
      (node (ref "R131") (pin "1") (pinfunction "1_1") (pintype "passive"))
      (node (ref "R132") (pin "1") (pinfunction "1_1") (pintype "passive"))
      (node (ref "R137") (pin "2") (pinfunction "2_2") (pintype "passive"))
    )
    (net (code "53") (name "Net-(R131-Pad2)") (class "Default")
      (node (ref "R131") (pin "2") (pinfunction "2_2") (pintype "passive"))
      (node (ref "R132") (pin "2") (pinfunction "2_2") (pintype "passive"))
      (node (ref "R133") (pin "1") (pinfunction "1_1") (pintype "passive"))
      (node (ref "R134") (pin "1") (pinfunction "1_1") (pintype "passive"))
    )
    (net (code "54") (name "Net-(R133-Pad2)") (class "Default")
      (node (ref "R133") (pin "2") (pinfunction "2_2") (pintype "passive"))
      (node (ref "R134") (pin "2") (pinfunction "2_2") (pintype "passive"))
      (node (ref "R135") (pin "1") (pinfunction "1_1") (pintype "passive"))
      (node (ref "R136") (pin "1") (pinfunction "1_1") (pintype "passive"))
    )
    (net (code "55") (name "Net-(U1-A)") (class "Default")
      (node (ref "R5") (pin "2") (pinfunction "2_2") (pintype "passive"))
      (node (ref "U1") (pin "1") (pinfunction "A_1") (pintype "bidirectional"))
    )
    (net (code "56") (name "Net-(U1-C)") (class "Default")
      (node (ref "J1") (pin "1") (pinfunction "1_1") (pintype "passive"))
      (node (ref "U1") (pin "4") (pinfunction "C_4") (pintype "bidirectional"))
    )
    (net (code "57") (name "Net-(U1-E)") (class "Default")
      (node (ref "J1") (pin "2") (pinfunction "2_2") (pintype "passive"))
      (node (ref "U1") (pin "3") (pinfunction "E_3") (pintype "bidirectional"))
    )
    (net (code "58") (name "Net-(U2-PB2)") (class "Default")
      (node (ref "R26") (pin "1") (pinfunction "1_1") (pintype "passive"))
      (node (ref "R27") (pin "2") (pinfunction "2_2") (pintype "passive"))
      (node (ref "TP2") (pin "TP") (pinfunction "TP_TP") (pintype "input"))
      (node (ref "U2") (pin "5") (pinfunction "PB2_5") (pintype "bidirectional"))
    )
    (net (code "59") (name "Net-(U3-A)") (class "Default")
      (node (ref "R33") (pin "2") (pinfunction "2_2") (pintype "passive"))
      (node (ref "U3") (pin "1") (pinfunction "A_1") (pintype "bidirectional"))
    )
    (net (code "60") (name "Net-(U3-C)") (class "Default")
      (node (ref "J6") (pin "1") (pinfunction "1_1") (pintype "passive"))
      (node (ref "U3") (pin "4") (pinfunction "C_4") (pintype "bidirectional"))
    )
    (net (code "61") (name "Net-(U3-E)") (class "Default")
      (node (ref "J6") (pin "2") (pinfunction "2_2") (pintype "passive"))
      (node (ref "U3") (pin "3") (pinfunction "E_3") (pintype "bidirectional"))
    )
    (net (code "62") (name "Net-(U4-PB2)") (class "Default")
      (node (ref "R3") (pin "1") (pinfunction "1_1") (pintype "passive"))
      (node (ref "R4") (pin "2") (pinfunction "2_2") (pintype "passive"))
      (node (ref "TP1") (pin "TP") (pinfunction "TP_TP") (pintype "input"))
      (node (ref "U4") (pin "5") (pinfunction "PB2_5") (pintype "bidirectional"))
    )
    (net (code "63") (name "Net-(U5-PB2)") (class "Default")
      (node (ref "R49") (pin "1") (pinfunction "1_1") (pintype "passive"))
      (node (ref "R50") (pin "2") (pinfunction "2_2") (pintype "passive"))
      (node (ref "TP3") (pin "TP") (pinfunction "TP_TP") (pintype "input"))
      (node (ref "U5") (pin "5") (pinfunction "PB2_5") (pintype "bidirectional"))
    )
    (net (code "64") (name "Net-(U6-A)") (class "Default")
      (node (ref "R56") (pin "2") (pinfunction "2_2") (pintype "passive"))
      (node (ref "U6") (pin "1") (pinfunction "A_1") (pintype "bidirectional"))
    )
    (net (code "65") (name "Net-(U6-C)") (class "Default")
      (node (ref "J10") (pin "1") (pinfunction "1_1") (pintype "passive"))
      (node (ref "U6") (pin "4") (pinfunction "C_4") (pintype "bidirectional"))
    )
    (net (code "66") (name "Net-(U6-E)") (class "Default")
      (node (ref "J10") (pin "2") (pinfunction "2_2") (pintype "passive"))
      (node (ref "U6") (pin "3") (pinfunction "E_3") (pintype "bidirectional"))
    )
    (net (code "67") (name "Net-(U7-PB2)") (class "Default")
      (node (ref "R72") (pin "1") (pinfunction "1_1") (pintype "passive"))
      (node (ref "R73") (pin "2") (pinfunction "2_2") (pintype "passive"))
      (node (ref "TP4") (pin "TP") (pinfunction "TP_TP") (pintype "input"))
      (node (ref "U7") (pin "5") (pinfunction "PB2_5") (pintype "bidirectional"))
    )
    (net (code "68") (name "Net-(U8-A)") (class "Default")
      (node (ref "R79") (pin "2") (pinfunction "2_2") (pintype "passive"))
      (node (ref "U8") (pin "1") (pinfunction "A_1") (pintype "bidirectional"))
    )
    (net (code "69") (name "Net-(U8-C)") (class "Default")
      (node (ref "J14") (pin "1") (pinfunction "1_1") (pintype "passive"))
      (node (ref "U8") (pin "4") (pinfunction "C_4") (pintype "bidirectional"))
    )
    (net (code "70") (name "Net-(U8-E)") (class "Default")
      (node (ref "J14") (pin "2") (pinfunction "2_2") (pintype "passive"))
      (node (ref "U8") (pin "3") (pinfunction "E_3") (pintype "bidirectional"))
    )
    (net (code "71") (name "Net-(U9-PB2)") (class "Default")
      (node (ref "R95") (pin "1") (pinfunction "1_1") (pintype "passive"))
      (node (ref "R96") (pin "2") (pinfunction "2_2") (pintype "passive"))
      (node (ref "TP5") (pin "TP") (pinfunction "TP_TP") (pintype "input"))
      (node (ref "U9") (pin "5") (pinfunction "PB2_5") (pintype "bidirectional"))
    )
    (net (code "72") (name "Net-(U10-A)") (class "Default")
      (node (ref "R102") (pin "2") (pinfunction "2_2") (pintype "passive"))
      (node (ref "U10") (pin "1") (pinfunction "A_1") (pintype "bidirectional"))
    )
    (net (code "73") (name "Net-(U10-C)") (class "Default")
      (node (ref "J18") (pin "1") (pinfunction "1_1") (pintype "passive"))
      (node (ref "U10") (pin "4") (pinfunction "C_4") (pintype "bidirectional"))
    )
    (net (code "74") (name "Net-(U10-E)") (class "Default")
      (node (ref "J18") (pin "2") (pinfunction "2_2") (pintype "passive"))
      (node (ref "U10") (pin "3") (pinfunction "E_3") (pintype "bidirectional"))
    )
    (net (code "75") (name "Net-(U11-PB2)") (class "Default")
      (node (ref "R118") (pin "1") (pinfunction "1_1") (pintype "passive"))
      (node (ref "R119") (pin "2") (pinfunction "2_2") (pintype "passive"))
      (node (ref "TP6") (pin "TP") (pinfunction "TP_TP") (pintype "input"))
      (node (ref "U11") (pin "5") (pinfunction "PB2_5") (pintype "bidirectional"))
    )
    (net (code "76") (name "Net-(U12-A)") (class "Default")
      (node (ref "R125") (pin "2") (pinfunction "2_2") (pintype "passive"))
      (node (ref "U12") (pin "1") (pinfunction "A_1") (pintype "bidirectional"))
    )
    (net (code "77") (name "Net-(U12-C)") (class "Default")
      (node (ref "J22") (pin "1") (pinfunction "1_1") (pintype "passive"))
      (node (ref "U12") (pin "4") (pinfunction "C_4") (pintype "bidirectional"))
    )
    (net (code "78") (name "Net-(U12-E)") (class "Default")
      (node (ref "J22") (pin "2") (pinfunction "2_2") (pintype "passive"))
      (node (ref "U12") (pin "3") (pinfunction "E_3") (pintype "bidirectional"))
    )
    (net (code "79") (name "PB0") (class "Default")
      (node (ref "R120") (pin "2") (pinfunction "2_2") (pintype "passive"))
      (node (ref "R21") (pin "2") (pinfunction "2_2") (pintype "passive"))
      (node (ref "R28") (pin "2") (pinfunction "2_2") (pintype "passive"))
      (node (ref "R51") (pin "2") (pinfunction "2_2") (pintype "passive"))
      (node (ref "R74") (pin "2") (pinfunction "2_2") (pintype "passive"))
      (node (ref "R97") (pin "2") (pinfunction "2_2") (pintype "passive"))
      (node (ref "SENSOR1") (pin "1") (pinfunction "1_1") (pintype "passive"))
      (node (ref "SENSOR2") (pin "1") (pinfunction "1_1") (pintype "passive"))
      (node (ref "SENSOR3") (pin "1") (pinfunction "1_1") (pintype "passive"))
      (node (ref "SENSOR4") (pin "1") (pinfunction "1_1") (pintype "passive"))
      (node (ref "SENSOR5") (pin "1") (pinfunction "1_1") (pintype "passive"))
      (node (ref "SENSOR6") (pin "1") (pinfunction "1_1") (pintype "passive"))
      (node (ref "U11") (pin "2") (pinfunction "PB0_2") (pintype "bidirectional"))
      (node (ref "U2") (pin "2") (pinfunction "PB0_2") (pintype "bidirectional"))
      (node (ref "U4") (pin "2") (pinfunction "PB0_2") (pintype "bidirectional"))
      (node (ref "U5") (pin "2") (pinfunction "PB0_2") (pintype "bidirectional"))
      (node (ref "U7") (pin "2") (pinfunction "PB0_2") (pintype "bidirectional"))
      (node (ref "U9") (pin "2") (pinfunction "PB0_2") (pintype "bidirectional"))
    )
    (net (code "80") (name "PB1") (class "Default")
      (node (ref "SENSOR1") (pin "3") (pinfunction "3_3") (pintype "passive"))
      (node (ref "SENSOR2") (pin "3") (pinfunction "3_3") (pintype "passive"))
      (node (ref "SENSOR3") (pin "3") (pinfunction "3_3") (pintype "passive"))
      (node (ref "SENSOR4") (pin "3") (pinfunction "3_3") (pintype "passive"))
      (node (ref "SENSOR5") (pin "3") (pinfunction "3_3") (pintype "passive"))
      (node (ref "SENSOR6") (pin "3") (pinfunction "3_3") (pintype "passive"))
      (node (ref "U11") (pin "3") (pinfunction "PB1_3") (pintype "bidirectional"))
      (node (ref "U2") (pin "3") (pinfunction "PB1_3") (pintype "bidirectional"))
      (node (ref "U4") (pin "3") (pinfunction "PB1_3") (pintype "bidirectional"))
      (node (ref "U5") (pin "3") (pinfunction "PB1_3") (pintype "bidirectional"))
      (node (ref "U7") (pin "3") (pinfunction "PB1_3") (pintype "bidirectional"))
      (node (ref "U9") (pin "3") (pinfunction "PB1_3") (pintype "bidirectional"))
    )
    (net (code "81") (name "RST") (class "Default")
      (node (ref "J13") (pin "5") (pinfunction "RST_5") (pintype "output"))
      (node (ref "J17") (pin "5") (pinfunction "RST_5") (pintype "output"))
      (node (ref "J2") (pin "5") (pinfunction "RST_5") (pintype "output"))
      (node (ref "J21") (pin "5") (pinfunction "RST_5") (pintype "output"))
      (node (ref "J5") (pin "5") (pinfunction "RST_5") (pintype "output"))
      (node (ref "J9") (pin "5") (pinfunction "RST_5") (pintype "output"))
      (node (ref "R1") (pin "2") (pinfunction "2_2") (pintype "passive"))
      (node (ref "R116") (pin "2") (pinfunction "2_2") (pintype "passive"))
      (node (ref "R24") (pin "2") (pinfunction "2_2") (pintype "passive"))
      (node (ref "R47") (pin "2") (pinfunction "2_2") (pintype "passive"))
      (node (ref "R70") (pin "2") (pinfunction "2_2") (pintype "passive"))
      (node (ref "R93") (pin "2") (pinfunction "2_2") (pintype "passive"))
      (node (ref "U11") (pin "4") (pinfunction "PB3_4") (pintype "bidirectional"))
      (node (ref "U2") (pin "4") (pinfunction "PB3_4") (pintype "bidirectional"))
      (node (ref "U4") (pin "4") (pinfunction "PB3_4") (pintype "bidirectional"))
      (node (ref "U5") (pin "4") (pinfunction "PB3_4") (pintype "bidirectional"))
      (node (ref "U7") (pin "4") (pinfunction "PB3_4") (pintype "bidirectional"))
      (node (ref "U9") (pin "4") (pinfunction "PB3_4") (pintype "bidirectional"))
    )
    (net (code "82") (name "RXD0") (class "Default")
      (node (ref "J11") (pin "2") (pinfunction "2_2") (pintype "passive"))
      (node (ref "J15") (pin "2") (pinfunction "2_2") (pintype "passive"))
      (node (ref "J19") (pin "2") (pinfunction "2_2") (pintype "passive"))
      (node (ref "J23") (pin "2") (pinfunction "2_2") (pintype "passive"))
      (node (ref "J3") (pin "2") (pinfunction "2_2") (pintype "passive"))
      (node (ref "J7") (pin "2") (pinfunction "2_2") (pintype "passive"))
      (node (ref "R103") (pin "1") (pinfunction "1_1") (pintype "passive"))
      (node (ref "R126") (pin "1") (pinfunction "1_1") (pintype "passive"))
      (node (ref "R16") (pin "1") (pinfunction "1_1") (pintype "passive"))
      (node (ref "R34") (pin "1") (pinfunction "1_1") (pintype "passive"))
      (node (ref "R57") (pin "1") (pinfunction "1_1") (pintype "passive"))
      (node (ref "R80") (pin "1") (pinfunction "1_1") (pintype "passive"))
      (node (ref "U11") (pin "11") (pinfunction "PA2_11") (pintype "bidirectional"))
      (node (ref "U2") (pin "11") (pinfunction "PA2_11") (pintype "bidirectional"))
      (node (ref "U4") (pin "11") (pinfunction "PA2_11") (pintype "bidirectional"))
      (node (ref "U5") (pin "11") (pinfunction "PA2_11") (pintype "bidirectional"))
      (node (ref "U7") (pin "11") (pinfunction "PA2_11") (pintype "bidirectional"))
      (node (ref "U9") (pin "11") (pinfunction "PA2_11") (pintype "bidirectional"))
    )
    (net (code "83") (name "SCK") (class "Default")
      (node (ref "J13") (pin "3") (pinfunction "SCK_3") (pintype "output"))
      (node (ref "J17") (pin "3") (pinfunction "SCK_3") (pintype "output"))
      (node (ref "J2") (pin "3") (pinfunction "SCK_3") (pintype "output"))
      (node (ref "J21") (pin "3") (pinfunction "SCK_3") (pintype "output"))
      (node (ref "J5") (pin "3") (pinfunction "SCK_3") (pintype "output"))
      (node (ref "J9") (pin "3") (pinfunction "SCK_3") (pintype "output"))
      (node (ref "R100") (pin "2") (pinfunction "2_2") (pintype "passive"))
      (node (ref "R101") (pin "1") (pinfunction "1_1") (pintype "passive"))
      (node (ref "R123") (pin "2") (pinfunction "2_2") (pintype "passive"))
      (node (ref "R124") (pin "1") (pinfunction "1_1") (pintype "passive"))
      (node (ref "R19") (pin "1") (pinfunction "1_1") (pintype "passive"))
      (node (ref "R20") (pin "2") (pinfunction "2_2") (pintype "passive"))
      (node (ref "R31") (pin "2") (pinfunction "2_2") (pintype "passive"))
      (node (ref "R32") (pin "1") (pinfunction "1_1") (pintype "passive"))
      (node (ref "R54") (pin "2") (pinfunction "2_2") (pintype "passive"))
      (node (ref "R55") (pin "1") (pinfunction "1_1") (pintype "passive"))
      (node (ref "R77") (pin "2") (pinfunction "2_2") (pintype "passive"))
      (node (ref "R78") (pin "1") (pinfunction "1_1") (pintype "passive"))
      (node (ref "U11") (pin "9") (pinfunction "PA4_9") (pintype "bidirectional"))
      (node (ref "U2") (pin "9") (pinfunction "PA4_9") (pintype "bidirectional"))
      (node (ref "U4") (pin "9") (pinfunction "PA4_9") (pintype "bidirectional"))
      (node (ref "U5") (pin "9") (pinfunction "PA4_9") (pintype "bidirectional"))
      (node (ref "U7") (pin "9") (pinfunction "PA4_9") (pintype "bidirectional"))
      (node (ref "U9") (pin "9") (pinfunction "PA4_9") (pintype "bidirectional"))
    )
    (net (code "84") (name "TXD0") (class "Default")
      (node (ref "R102") (pin "1") (pinfunction "1_1") (pintype "passive"))
      (node (ref "R125") (pin "1") (pinfunction "1_1") (pintype "passive"))
      (node (ref "R33") (pin "1") (pinfunction "1_1") (pintype "passive"))
      (node (ref "R5") (pin "1") (pinfunction "1_1") (pintype "passive"))
      (node (ref "R56") (pin "1") (pinfunction "1_1") (pintype "passive"))
      (node (ref "R79") (pin "1") (pinfunction "1_1") (pintype "passive"))
      (node (ref "U11") (pin "12") (pinfunction "PA1_12") (pintype "bidirectional"))
      (node (ref "U2") (pin "12") (pinfunction "PA1_12") (pintype "bidirectional"))
      (node (ref "U4") (pin "12") (pinfunction "PA1_12") (pintype "bidirectional"))
      (node (ref "U5") (pin "12") (pinfunction "PA1_12") (pintype "bidirectional"))
      (node (ref "U7") (pin "12") (pinfunction "PA1_12") (pintype "bidirectional"))
      (node (ref "U9") (pin "12") (pinfunction "PA1_12") (pintype "bidirectional"))
    )
    (net (code "85") (name "VCC") (class "Default")
      (node (ref "C1") (pin "1") (pinfunction "1_1") (pintype "passive"))
      (node (ref "C10") (pin "1") (pinfunction "1_1") (pintype "passive"))
      (node (ref "C13") (pin "1") (pinfunction "1_1") (pintype "passive"))
      (node (ref "C16") (pin "1") (pinfunction "1_1") (pintype "passive"))
      (node (ref "C4") (pin "1") (pinfunction "1_1") (pintype "passive"))
      (node (ref "C7") (pin "1") (pinfunction "1_1") (pintype "passive"))
      (node (ref "D12") (pin "A") (pinfunction "A_A") (pintype "passive"))
      (node (ref "D16") (pin "A") (pinfunction "A_A") (pintype "passive"))
      (node (ref "D20") (pin "A") (pinfunction "A_A") (pintype "passive"))
      (node (ref "D24") (pin "A") (pinfunction "A_A") (pintype "passive"))
      (node (ref "D3") (pin "A") (pinfunction "A_A") (pintype "passive"))
      (node (ref "D8") (pin "A") (pinfunction "A_A") (pintype "passive"))
      (node (ref "J11") (pin "1") (pinfunction "1_1") (pintype "passive"))
      (node (ref "J12") (pin "1") (pinfunction "1_1") (pintype "passive"))
      (node (ref "J13") (pin "2") (pinfunction "VCC_2") (pintype "power_in"))
      (node (ref "J15") (pin "1") (pinfunction "1_1") (pintype "passive"))
      (node (ref "J16") (pin "1") (pinfunction "1_1") (pintype "passive"))
      (node (ref "J17") (pin "2") (pinfunction "VCC_2") (pintype "power_in"))
      (node (ref "J19") (pin "1") (pinfunction "1_1") (pintype "passive"))
      (node (ref "J2") (pin "2") (pinfunction "VCC_2") (pintype "power_in"))
      (node (ref "J20") (pin "1") (pinfunction "1_1") (pintype "passive"))
      (node (ref "J21") (pin "2") (pinfunction "VCC_2") (pintype "power_in"))
      (node (ref "J23") (pin "1") (pinfunction "1_1") (pintype "passive"))
      (node (ref "J24") (pin "1") (pinfunction "1_1") (pintype "passive"))
      (node (ref "J3") (pin "1") (pinfunction "1_1") (pintype "passive"))
      (node (ref "J4") (pin "1") (pinfunction "1_1") (pintype "passive"))
      (node (ref "J5") (pin "2") (pinfunction "VCC_2") (pintype "power_in"))
      (node (ref "J7") (pin "1") (pinfunction "1_1") (pintype "passive"))
      (node (ref "J8") (pin "1") (pinfunction "1_1") (pintype "passive"))
      (node (ref "J9") (pin "2") (pinfunction "VCC_2") (pintype "power_in"))
      (node (ref "R1") (pin "1") (pinfunction "1_1") (pintype "passive"))
      (node (ref "R106") (pin "1") (pinfunction "1_1") (pintype "passive"))
      (node (ref "R107") (pin "1") (pinfunction "1_1") (pintype "passive"))
      (node (ref "R114") (pin "1") (pinfunction "1_1") (pintype "passive"))
      (node (ref "R116") (pin "1") (pinfunction "1_1") (pintype "passive"))
      (node (ref "R129") (pin "1") (pinfunction "1_1") (pintype "passive"))
      (node (ref "R130") (pin "1") (pinfunction "1_1") (pintype "passive"))
      (node (ref "R137") (pin "1") (pinfunction "1_1") (pintype "passive"))
      (node (ref "R22") (pin "1") (pinfunction "1_1") (pintype "passive"))
      (node (ref "R24") (pin "1") (pinfunction "1_1") (pintype "passive"))
      (node (ref "R37") (pin "1") (pinfunction "1_1") (pintype "passive"))
      (node (ref "R38") (pin "1") (pinfunction "1_1") (pintype "passive"))
      (node (ref "R45") (pin "1") (pinfunction "1_1") (pintype "passive"))
      (node (ref "R47") (pin "1") (pinfunction "1_1") (pintype "passive"))
      (node (ref "R6") (pin "1") (pinfunction "1_1") (pintype "passive"))
      (node (ref "R60") (pin "1") (pinfunction "1_1") (pintype "passive"))
      (node (ref "R61") (pin "1") (pinfunction "1_1") (pintype "passive"))
      (node (ref "R68") (pin "1") (pinfunction "1_1") (pintype "passive"))
      (node (ref "R7") (pin "1") (pinfunction "1_1") (pintype "passive"))
      (node (ref "R70") (pin "1") (pinfunction "1_1") (pintype "passive"))
      (node (ref "R83") (pin "1") (pinfunction "1_1") (pintype "passive"))
      (node (ref "R84") (pin "1") (pinfunction "1_1") (pintype "passive"))
      (node (ref "R91") (pin "1") (pinfunction "1_1") (pintype "passive"))
      (node (ref "R93") (pin "1") (pinfunction "1_1") (pintype "passive"))
      (node (ref "U11") (pin "1") (pinfunction "VCC_1") (pintype "bidirectional"))
      (node (ref "U2") (pin "1") (pinfunction "VCC_1") (pintype "bidirectional"))
      (node (ref "U4") (pin "1") (pinfunction "VCC_1") (pintype "bidirectional"))
      (node (ref "U5") (pin "1") (pinfunction "VCC_1") (pintype "bidirectional"))
      (node (ref "U7") (pin "1") (pinfunction "VCC_1") (pintype "bidirectional"))
      (node (ref "U9") (pin "1") (pinfunction "VCC_1") (pintype "bidirectional"))
    )
  )
)
